# A314-600_v1_0.net
KiCad netlist of a schematic drawn in EAGLE
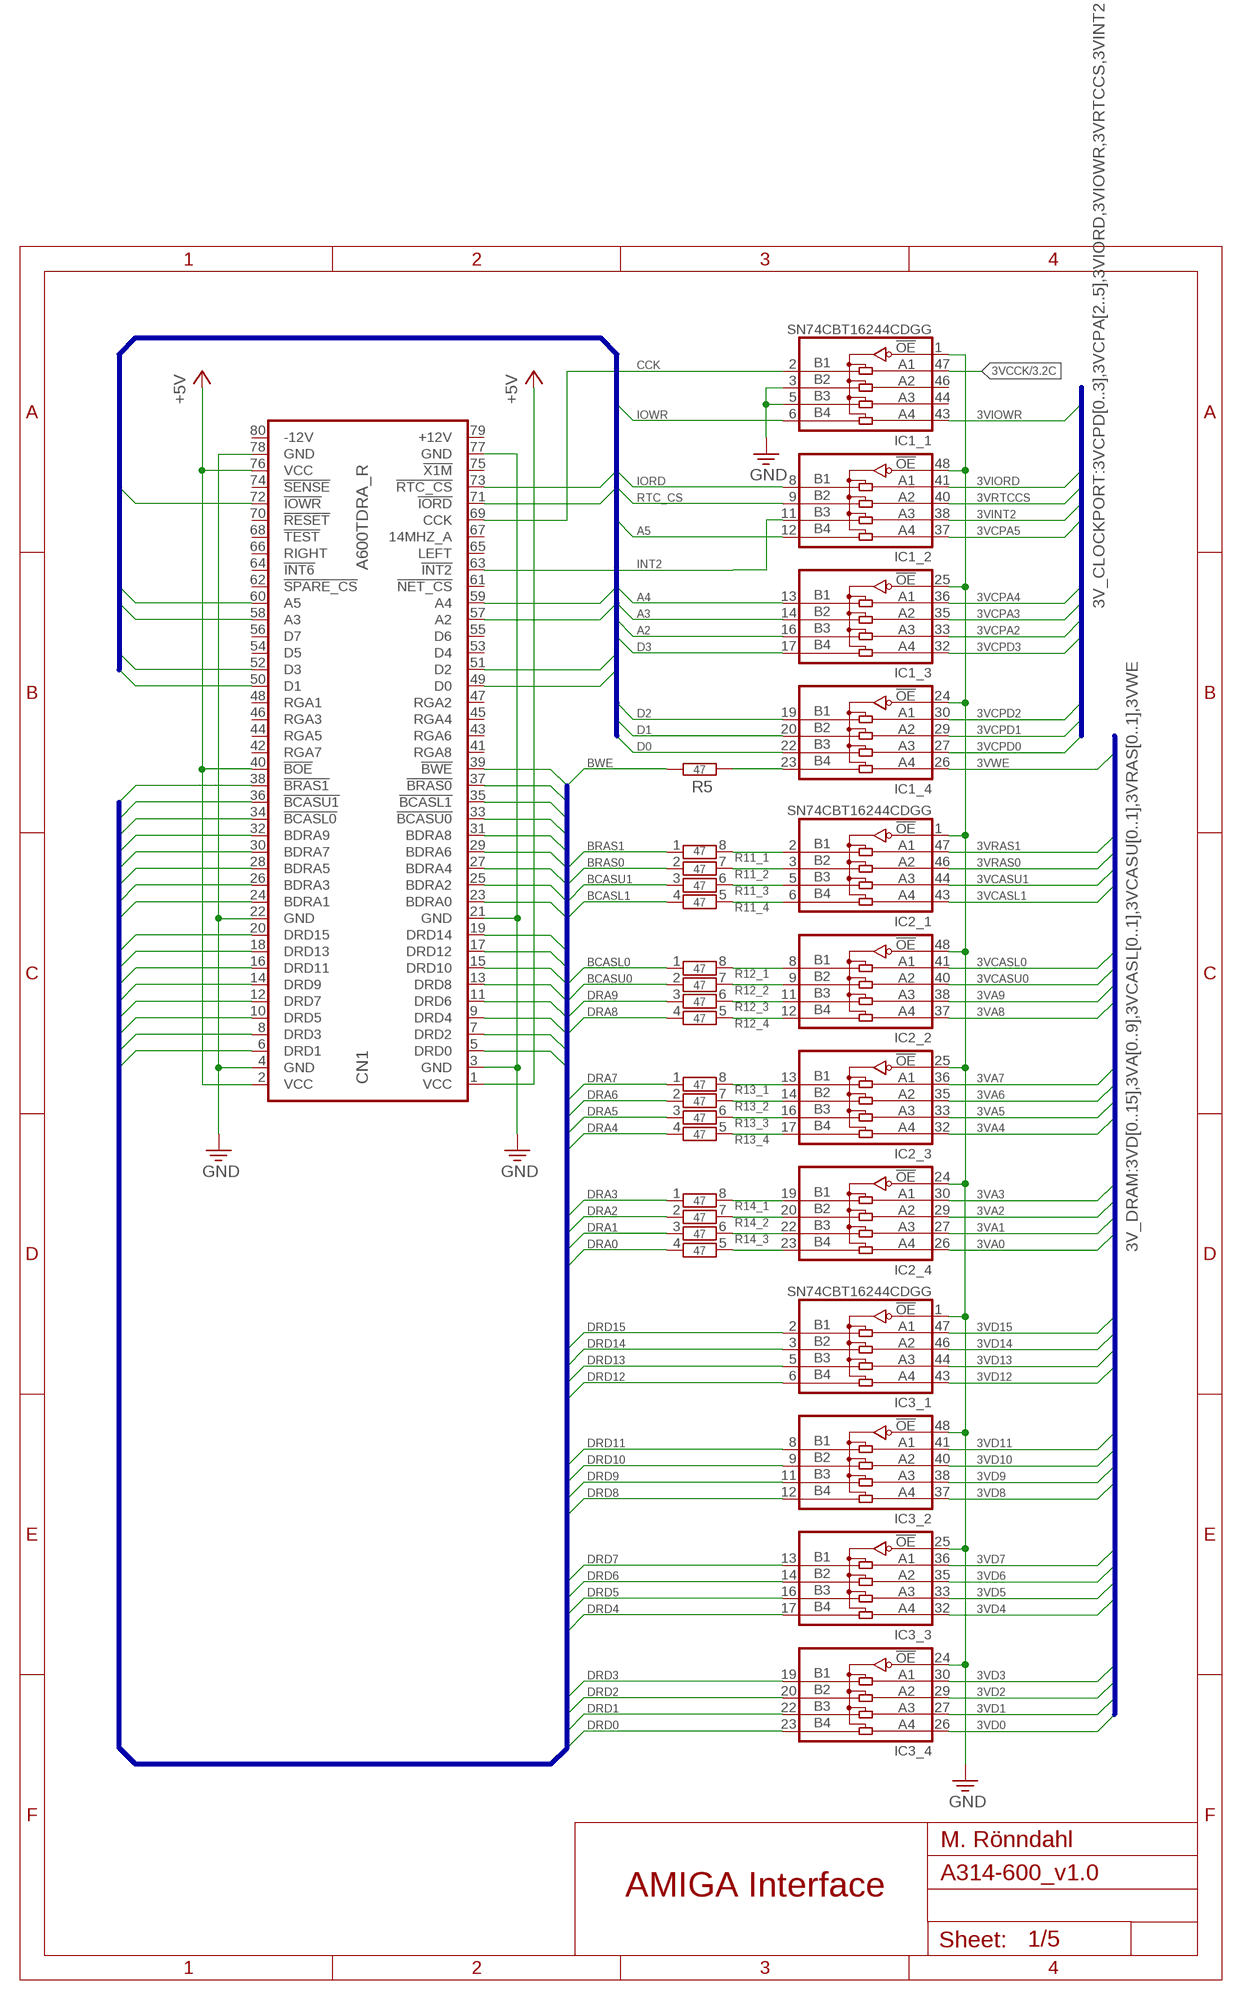
[diagram p0: schematic, sheet 1]
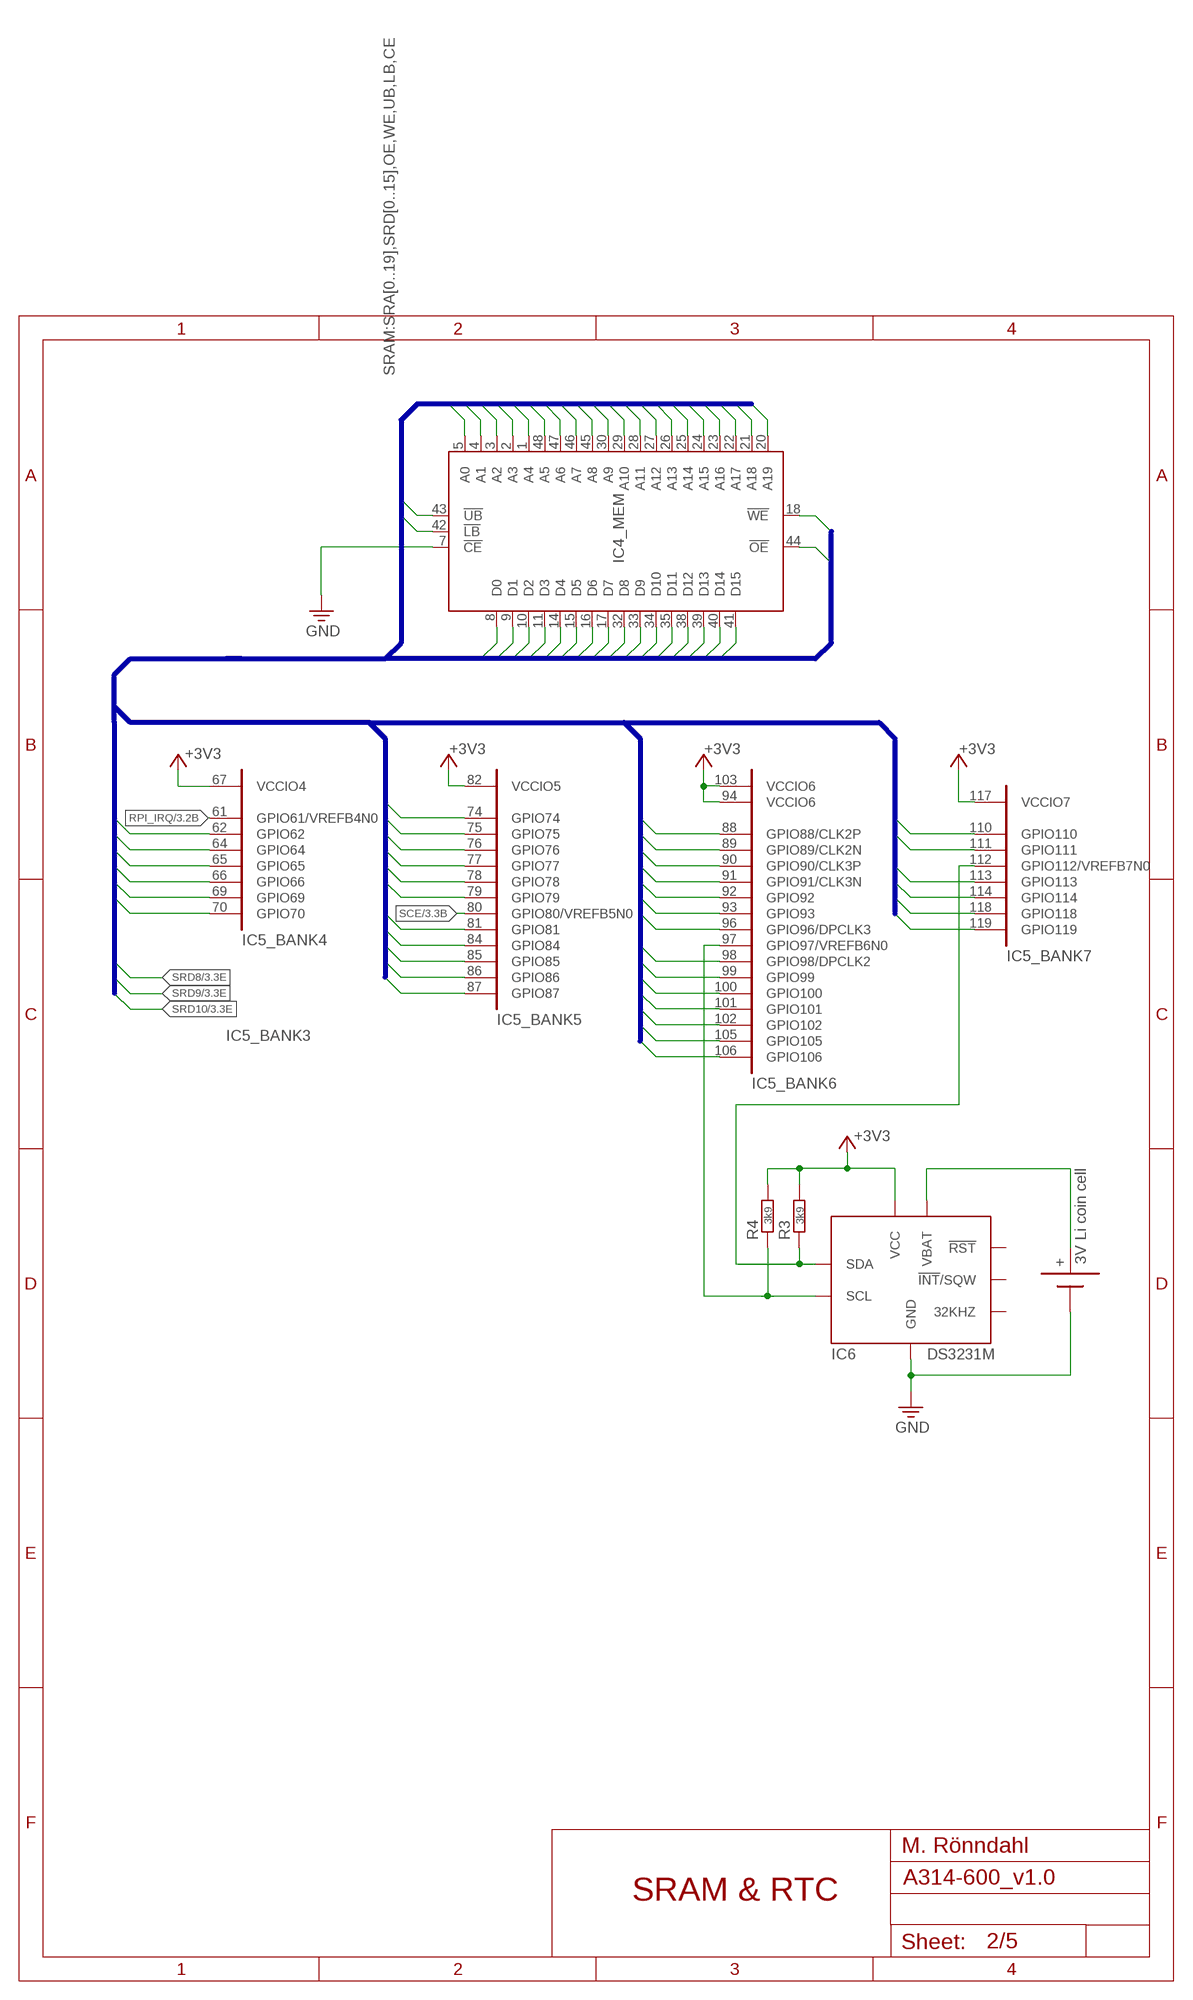
[diagram p1: schematic, sheet 2]
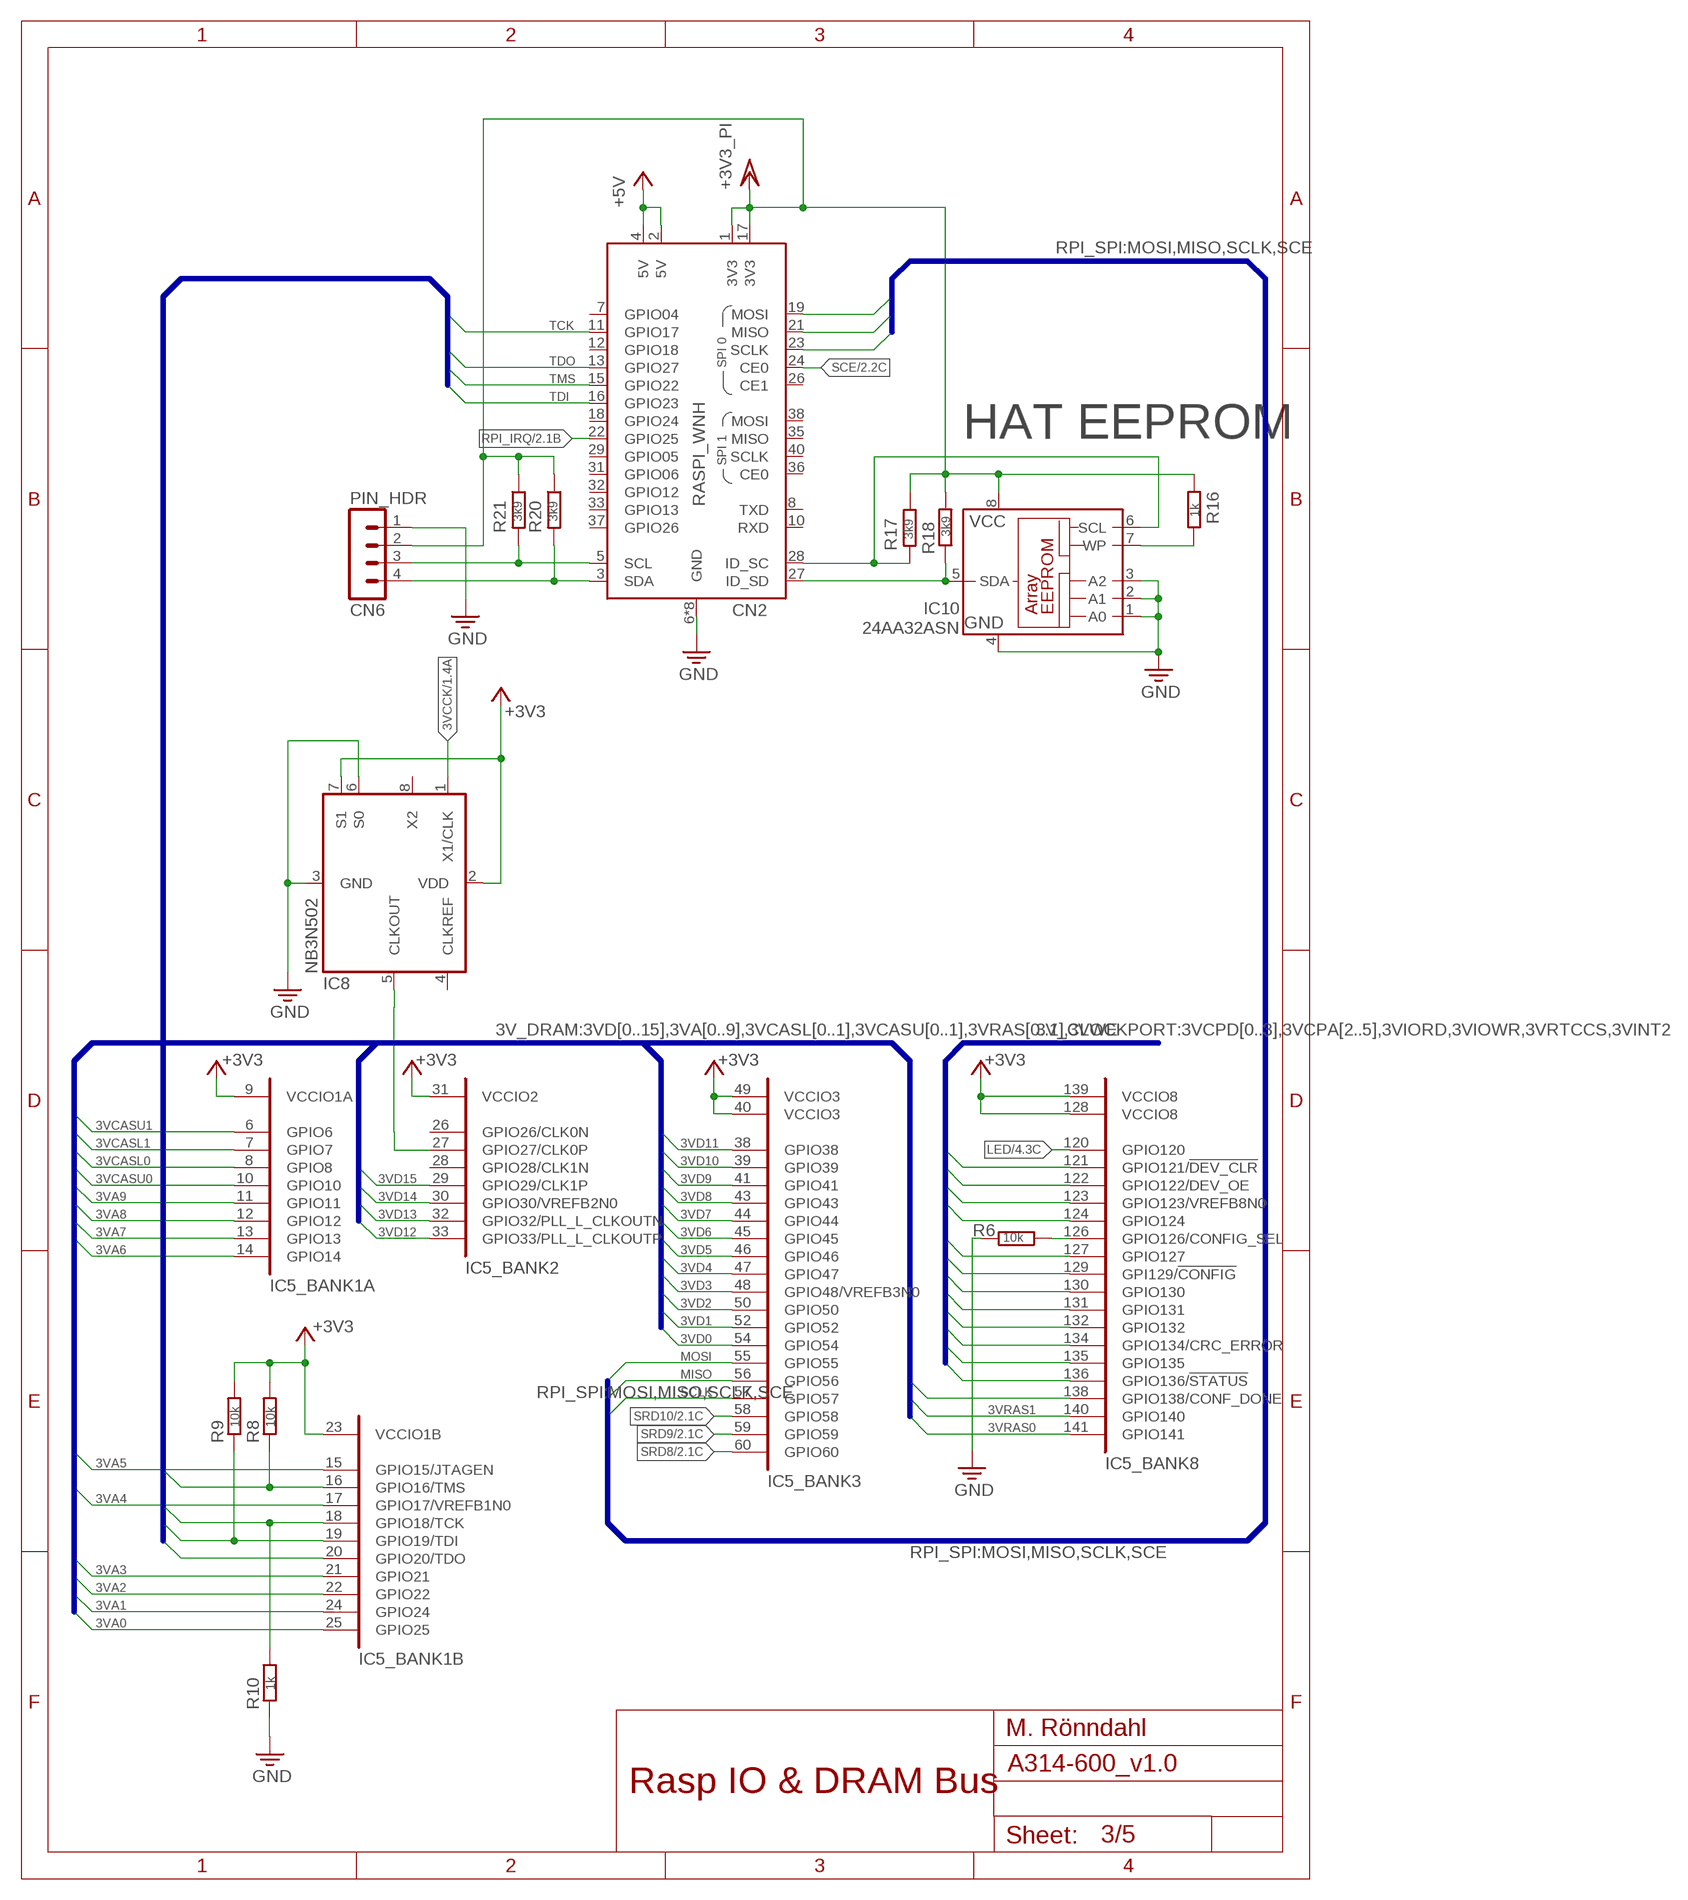
[diagram p2: schematic, sheet 3]
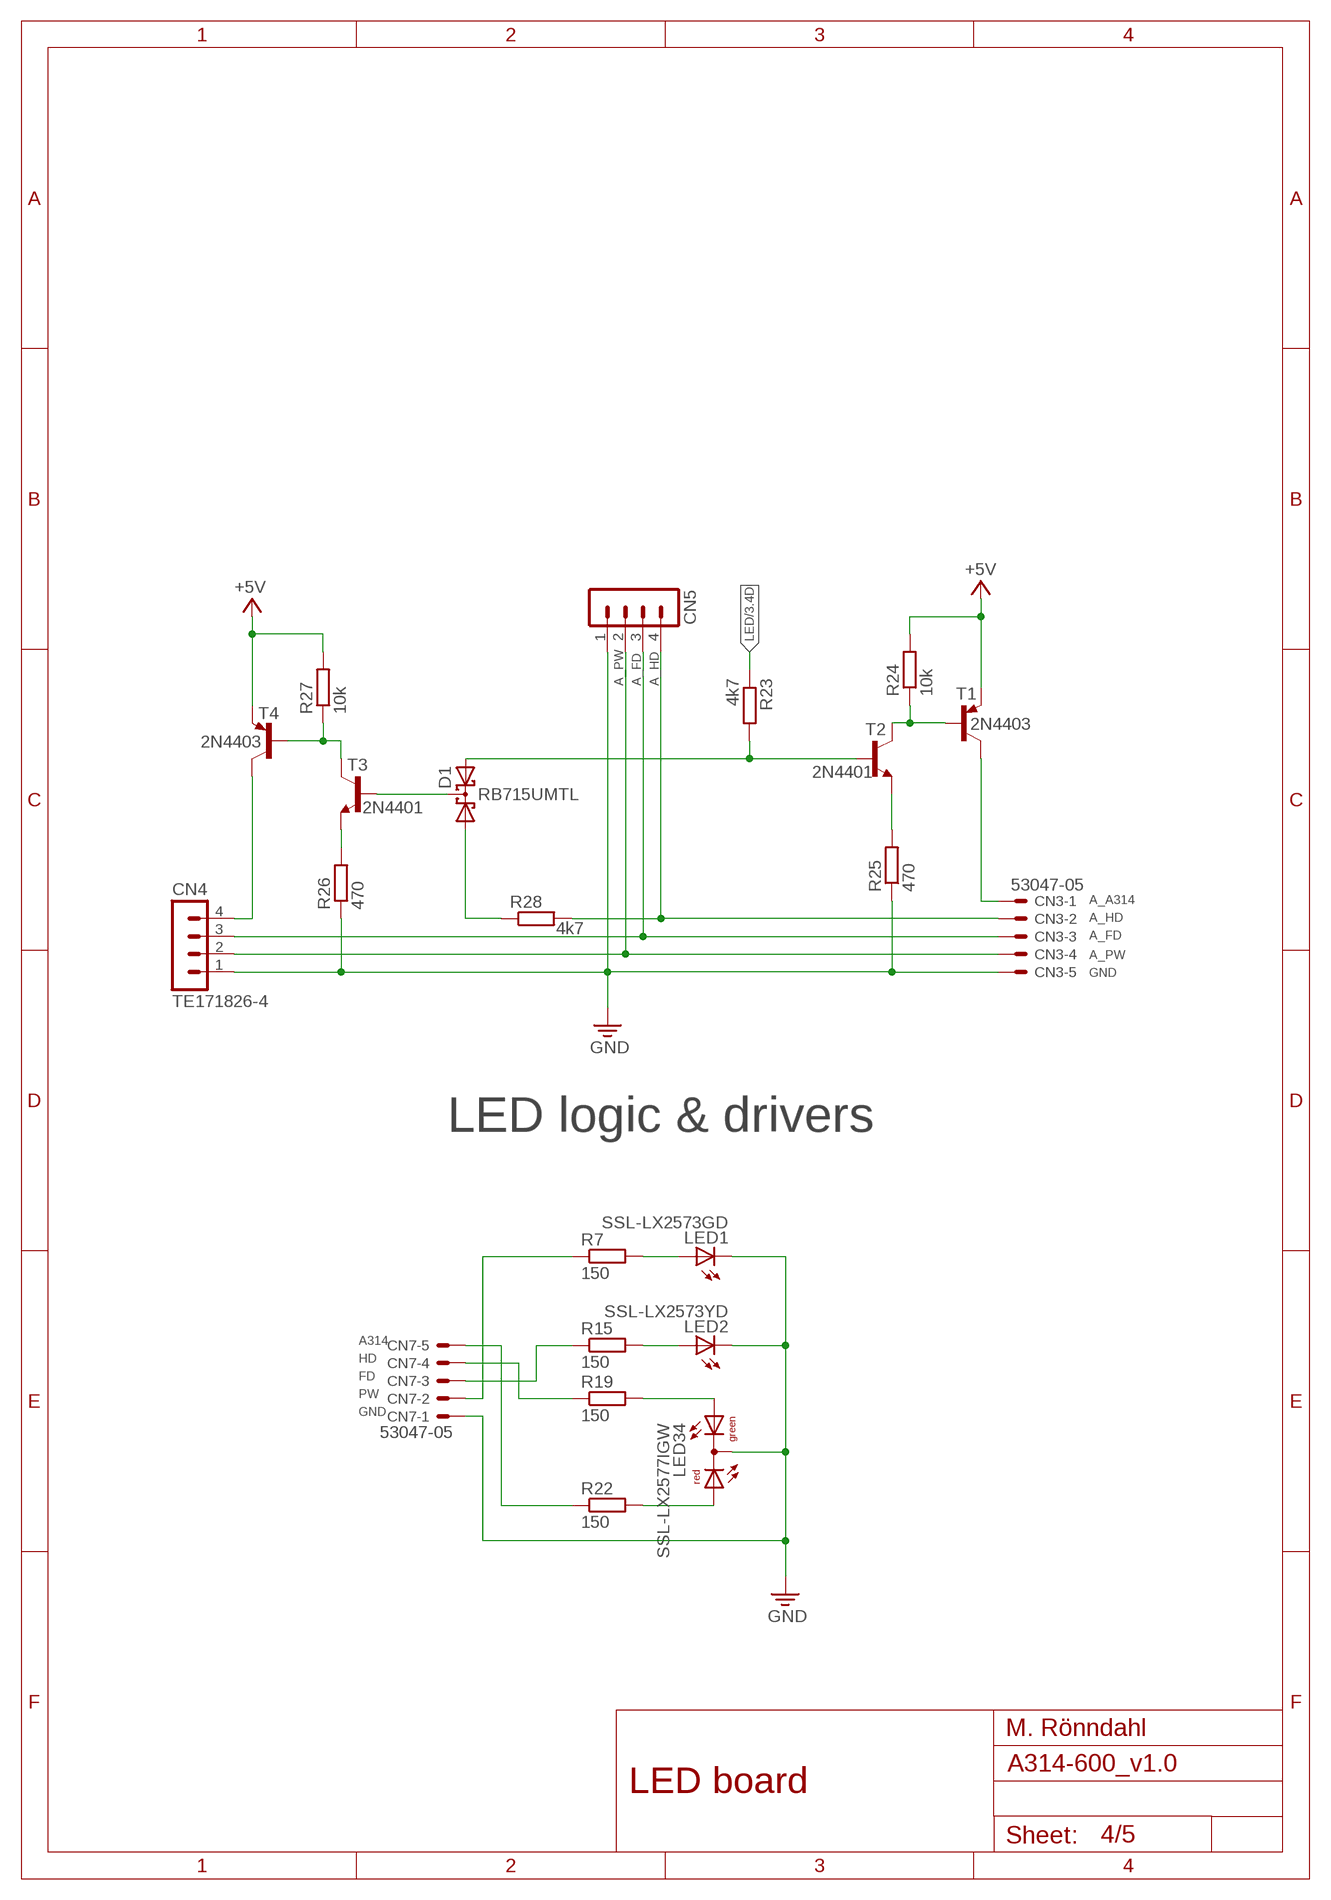
[diagram p3: schematic, sheet 4]
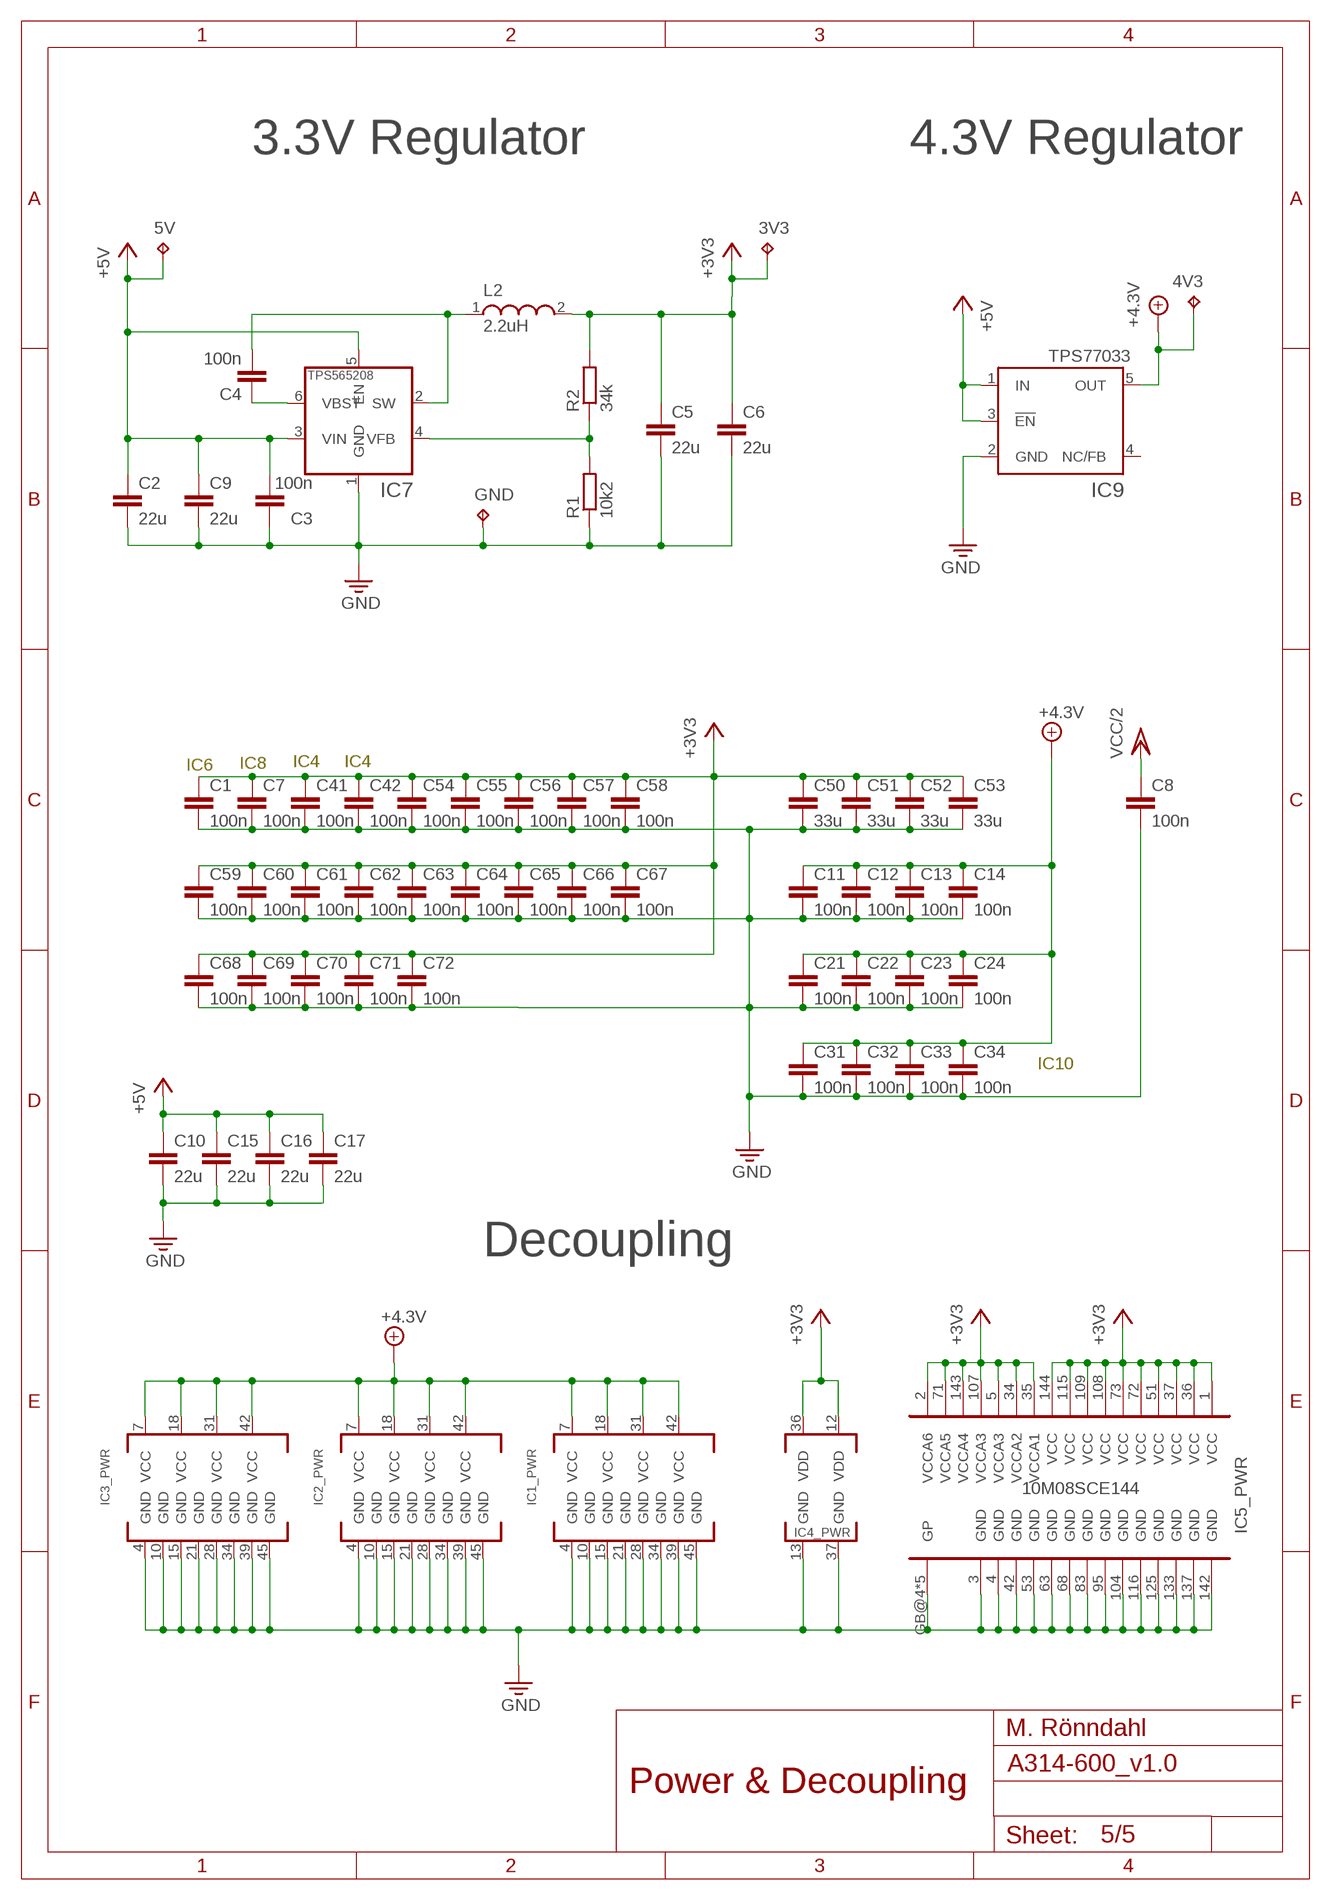
[diagram p4: schematic, sheet 5]

(export (version "E")
  (design (tool "Eeschema 10.0.6"))
  (components
    (comp (ref "CN2")
      (value "RASPI_WNH")
      (footprint "eagle-import:RASPBERRYPIZEROW_NO_HOLES")
      (libsource (lib "eagle-import") (part "RASPI_WNH"))
    )
    (comp (ref "CN6")
      (value "PIN_HDR")
      (footprint "eagle-import:MA04-1")
      (libsource (lib "eagle-import") (part "MA04-1"))
    )
    (comp (ref "IC5")
      (value "10M08SCE144")
      (footprint "eagle-import:SQFP-S-20X20-144")
      (libsource (lib "eagle-import") (part "10M08SCE144"))
    )
    (comp (ref "IC8")
      (value "NB3N502")
      (footprint "eagle-import:SO08")
      (libsource (lib "eagle-import") (part "NB3N502"))
    )
    (comp (ref "IC10")
      (value "24AA32ASN")
      (footprint "eagle-import:SO-08")
      (fields (field (name "MF") "MICROCHIP") (field (name "MPN") "24AA32A-I/SN"))
      (libsource (lib "eagle-import") (part "24SNAA32A"))
    )
    (comp (ref "R6")
      (value "10k")
      (footprint "eagle-import:R0603")
      (libsource (lib "eagle-import") (part "R-EU_R0603"))
    )
    (comp (ref "R8")
      (value "10k")
      (footprint "eagle-import:R0603")
      (libsource (lib "eagle-import") (part "R-EU_R0603"))
    )
    (comp (ref "R9")
      (value "10k")
      (footprint "eagle-import:R0603")
      (libsource (lib "eagle-import") (part "R-EU_R0603"))
    )
    (comp (ref "R10")
      (value "1k")
      (footprint "eagle-import:R0603")
      (libsource (lib "eagle-import") (part "R-EU_R0603"))
    )
    (comp (ref "R16")
      (value "1k")
      (footprint "eagle-import:R0603")
      (libsource (lib "eagle-import") (part "R-EU_R0603"))
    )
    (comp (ref "R17")
      (value "3k9")
      (footprint "eagle-import:R0603")
      (libsource (lib "eagle-import") (part "R-EU_R0603"))
    )
    (comp (ref "R18")
      (value "3k9")
      (footprint "eagle-import:R0603")
      (libsource (lib "eagle-import") (part "R-EU_R0603"))
    )
    (comp (ref "R20")
      (value "3k9")
      (footprint "eagle-import:R0603")
      (libsource (lib "eagle-import") (part "R-EU_R0603"))
    )
    (comp (ref "R21")
      (value "3k9")
      (footprint "eagle-import:R0603")
      (libsource (lib "eagle-import") (part "R-EU_R0603"))
    )
    (comp (ref "CN1")
      (value "A600TDRA_R")
      (footprint "eagle-import:CE-2X40_1.27_R")
      (libsource (lib "eagle-import") (part "A600TDRA_R"))
    )
    (comp (ref "IC1")
      (value "SN74CBT16244CDGG")
      (footprint "eagle-import:PSOP-DGG48")
      (libsource (lib "eagle-import") (part "SN74CBT16244CDGG"))
    )
    (comp (ref "IC2")
      (value "SN74CBT16244CDGG")
      (footprint "eagle-import:PSOP-DGG48")
      (libsource (lib "eagle-import") (part "SN74CBT16244CDGG"))
    )
    (comp (ref "IC3")
      (value "SN74CBT16244CDGG")
      (footprint "eagle-import:PSOP-DGG48")
      (libsource (lib "eagle-import") (part "SN74CBT16244CDGG"))
    )
    (comp (ref "R5")
      (value "47")
      (footprint "eagle-import:R0603")
      (libsource (lib "eagle-import") (part "R-EU_R0603"))
    )
    (comp (ref "R11")
      (value "47")
      (footprint "eagle-import:CTS742C083")
      (libsource (lib "eagle-import") (part "CTS742C083_S"))
    )
    (comp (ref "R12")
      (value "47")
      (footprint "eagle-import:CTS742C083")
      (libsource (lib "eagle-import") (part "CTS742C083_S"))
    )
    (comp (ref "R13")
      (value "47")
      (footprint "eagle-import:CTS742C083")
      (libsource (lib "eagle-import") (part "CTS742C083_S"))
    )
    (comp (ref "R14")
      (value "47")
      (footprint "eagle-import:CTS742C083")
      (libsource (lib "eagle-import") (part "CTS742C083_S"))
    )
    (comp (ref "BAT1")
      (value "CR2025/CR2032TH")
      (footprint "eagle-import:LINX20XX-THM")
      (libsource (lib "eagle-import") (part "CR2025/CR2032TH"))
    )
    (comp (ref "IC4")
      (value "IS61WV102416FBLL-TLI")
      (footprint "eagle-import:TSOP-1_48L_12X20")
      (libsource (lib "eagle-import") (part "IS61WV102416FBLL-TLI"))
    )
    (comp (ref "IC6")
      (value "DS3231M")
      (footprint "eagle-import:SOIC8")
      (libsource (lib "eagle-import") (part "DS3231M"))
    )
    (comp (ref "R3")
      (value "3k9")
      (footprint "eagle-import:R0603")
      (libsource (lib "eagle-import") (part "R-EU_R0603"))
    )
    (comp (ref "R4")
      (value "3k9")
      (footprint "eagle-import:R0603")
      (libsource (lib "eagle-import") (part "R-EU_R0603"))
    )
    (comp (ref "CN3")
      (value "53047-05")
      (footprint "eagle-import:53047-05")
      (fields (field (name "MF") "MOLEX") (field (name "MPN") "53047-0510"))
      (libsource (lib "eagle-import") (part "53?-05047"))
    )
    (comp (ref "CN4")
      (value "TE171826-4")
      (footprint "eagle-import:FLOPPY_PWR")
      (libsource (lib "eagle-import") (part "TE171826-4"))
    )
    (comp (ref "CN5")
      (value "MA04-1")
      (footprint "eagle-import:MA04-1")
      (libsource (lib "eagle-import") (part "con-various_MA04-1"))
    )
    (comp (ref "CN7")
      (value "53047-05")
      (footprint "eagle-import:53047-05")
      (fields (field (name "MF") "MOLEX") (field (name "MPN") "53047-0510"))
      (libsource (lib "eagle-import") (part "53?-05047"))
    )
    (comp (ref "D1")
      (value "RB715UMTL")
      (footprint "eagle-import:SOT23")
      (libsource (lib "eagle-import") (part "BAS40-05"))
    )
    (comp (ref "LED1")
      (value "SSL-LX2573GD")
      (footprint "eagle-import:LED2X5")
      (libsource (lib "eagle-import") (part "LEDSQR2X5"))
    )
    (comp (ref "LED2")
      (value "SSL-LX2573YD")
      (footprint "eagle-import:LED2X5")
      (libsource (lib "eagle-import") (part "LEDSQR2X5"))
    )
    (comp (ref "LED34")
      (value "SSL-LX2577IGW")
      (footprint "eagle-import:DUOLED2X5")
      (libsource (lib "eagle-import") (part "DUOLED2X5"))
    )
    (comp (ref "R7")
      (value "150")
      (footprint "eagle-import:R0603")
      (libsource (lib "eagle-import") (part "R-EU_R0603"))
    )
    (comp (ref "R15")
      (value "150")
      (footprint "eagle-import:R0603")
      (libsource (lib "eagle-import") (part "R-EU_R0603"))
    )
    (comp (ref "R19")
      (value "150")
      (footprint "eagle-import:R0603")
      (libsource (lib "eagle-import") (part "R-EU_R0603"))
    )
    (comp (ref "R22")
      (value "150")
      (footprint "eagle-import:R0603")
      (libsource (lib "eagle-import") (part "R-EU_R0603"))
    )
    (comp (ref "R23")
      (value "4k7")
      (footprint "eagle-import:R0603")
      (libsource (lib "eagle-import") (part "R-EU_R0603"))
    )
    (comp (ref "R24")
      (value "10k")
      (footprint "eagle-import:R0603")
      (libsource (lib "eagle-import") (part "R-EU_R0603"))
    )
    (comp (ref "R25")
      (value "470")
      (footprint "eagle-import:R0603")
      (libsource (lib "eagle-import") (part "R-EU_R0603"))
    )
    (comp (ref "R26")
      (value "470")
      (footprint "eagle-import:R0603")
      (libsource (lib "eagle-import") (part "R-EU_R0603"))
    )
    (comp (ref "R27")
      (value "10k")
      (footprint "eagle-import:R0603")
      (libsource (lib "eagle-import") (part "R-EU_R0603"))
    )
    (comp (ref "R28")
      (value "4k7")
      (footprint "eagle-import:R0603")
      (libsource (lib "eagle-import") (part "R-EU_R0603"))
    )
    (comp (ref "T1")
      (value "2N4403")
      (footprint "eagle-import:SOT23-BEC")
      (libsource (lib "eagle-import") (part "-PNP-SOT23-BECMMBT4403LT1"))
    )
    (comp (ref "T2")
      (value "2N4401")
      (footprint "eagle-import:SOT23-BEC")
      (libsource (lib "eagle-import") (part "-NPN-SOT23-BECMMBT4401LT1"))
    )
    (comp (ref "T3")
      (value "2N4401")
      (footprint "eagle-import:SOT23-BEC")
      (libsource (lib "eagle-import") (part "-NPN-SOT23-BECMMBT4401LT1"))
    )
    (comp (ref "T4")
      (value "2N4403")
      (footprint "eagle-import:SOT23-BEC")
      (libsource (lib "eagle-import") (part "-PNP-SOT23-BECMMBT4403LT1"))
    )
    (comp (ref "3V3")
      (value "TPPAD1-13")
      (footprint "eagle-import:P1-13")
      (libsource (lib "eagle-import") (part "TPPAD1-13"))
    )
    (comp (ref "4V3")
      (value "TPPAD1-13")
      (footprint "eagle-import:P1-13")
      (libsource (lib "eagle-import") (part "TPPAD1-13"))
    )
    (comp (ref "5V")
      (value "TPPAD1-13")
      (footprint "eagle-import:P1-13")
      (libsource (lib "eagle-import") (part "TPPAD1-13"))
    )
    (comp (ref "C1")
      (value "100n")
      (footprint "eagle-import:C0603")
      (libsource (lib "eagle-import") (part "C-EUC0603"))
    )
    (comp (ref "C2")
      (value "22u")
      (footprint "eagle-import:C0805")
      (libsource (lib "eagle-import") (part "C-EUC0805"))
    )
    (comp (ref "C3")
      (value "100n")
      (footprint "eagle-import:C0603")
      (libsource (lib "eagle-import") (part "C-EUC0603"))
    )
    (comp (ref "C4")
      (value "100n")
      (footprint "eagle-import:C0603")
      (libsource (lib "eagle-import") (part "C-EUC0603"))
    )
    (comp (ref "C5")
      (value "22u")
      (footprint "eagle-import:C0805")
      (libsource (lib "eagle-import") (part "C-EUC0805"))
    )
    (comp (ref "C6")
      (value "22u")
      (footprint "eagle-import:C0805")
      (libsource (lib "eagle-import") (part "C-EUC0805"))
    )
    (comp (ref "C7")
      (value "100n")
      (footprint "eagle-import:C0603")
      (libsource (lib "eagle-import") (part "C-EUC0603"))
    )
    (comp (ref "C8")
      (value "100n")
      (footprint "eagle-import:C0603")
      (libsource (lib "eagle-import") (part "C-EUC0603"))
    )
    (comp (ref "C9")
      (value "22u")
      (footprint "eagle-import:C0805")
      (libsource (lib "eagle-import") (part "C-EUC0805"))
    )
    (comp (ref "C10")
      (value "22u")
      (footprint "eagle-import:C0805")
      (libsource (lib "eagle-import") (part "C-EUC0805"))
    )
    (comp (ref "C11")
      (value "100n")
      (footprint "eagle-import:C0603")
      (libsource (lib "eagle-import") (part "C-EUC0603"))
    )
    (comp (ref "C12")
      (value "100n")
      (footprint "eagle-import:C0603")
      (libsource (lib "eagle-import") (part "C-EUC0603"))
    )
    (comp (ref "C13")
      (value "100n")
      (footprint "eagle-import:C0603")
      (libsource (lib "eagle-import") (part "C-EUC0603"))
    )
    (comp (ref "C14")
      (value "100n")
      (footprint "eagle-import:C0603")
      (libsource (lib "eagle-import") (part "C-EUC0603"))
    )
    (comp (ref "C15")
      (value "22u")
      (footprint "eagle-import:C0805")
      (libsource (lib "eagle-import") (part "C-EUC0805"))
    )
    (comp (ref "C16")
      (value "22u")
      (footprint "eagle-import:C0805")
      (libsource (lib "eagle-import") (part "C-EUC0805"))
    )
    (comp (ref "C17")
      (value "22u")
      (footprint "eagle-import:C0805")
      (libsource (lib "eagle-import") (part "C-EUC0805"))
    )
    (comp (ref "C21")
      (value "100n")
      (footprint "eagle-import:C0603")
      (libsource (lib "eagle-import") (part "C-EUC0603"))
    )
    (comp (ref "C22")
      (value "100n")
      (footprint "eagle-import:C0603")
      (libsource (lib "eagle-import") (part "C-EUC0603"))
    )
    (comp (ref "C23")
      (value "100n")
      (footprint "eagle-import:C0603")
      (libsource (lib "eagle-import") (part "C-EUC0603"))
    )
    (comp (ref "C24")
      (value "100n")
      (footprint "eagle-import:C0603")
      (libsource (lib "eagle-import") (part "C-EUC0603"))
    )
    (comp (ref "C31")
      (value "100n")
      (footprint "eagle-import:C0603")
      (libsource (lib "eagle-import") (part "C-EUC0603"))
    )
    (comp (ref "C32")
      (value "100n")
      (footprint "eagle-import:C0603")
      (libsource (lib "eagle-import") (part "C-EUC0603"))
    )
    (comp (ref "C33")
      (value "100n")
      (footprint "eagle-import:C0603")
      (libsource (lib "eagle-import") (part "C-EUC0603"))
    )
    (comp (ref "C34")
      (value "100n")
      (footprint "eagle-import:C0603")
      (libsource (lib "eagle-import") (part "C-EUC0603"))
    )
    (comp (ref "C41")
      (value "100n")
      (footprint "eagle-import:C0603")
      (libsource (lib "eagle-import") (part "C-EUC0603"))
    )
    (comp (ref "C42")
      (value "100n")
      (footprint "eagle-import:C0603")
      (libsource (lib "eagle-import") (part "C-EUC0603"))
    )
    (comp (ref "C50")
      (value "33u")
      (footprint "eagle-import:C0805")
      (libsource (lib "eagle-import") (part "C-EUC0805"))
    )
    (comp (ref "C51")
      (value "33u")
      (footprint "eagle-import:C0805")
      (libsource (lib "eagle-import") (part "C-EUC0805"))
    )
    (comp (ref "C52")
      (value "33u")
      (footprint "eagle-import:C0805")
      (libsource (lib "eagle-import") (part "C-EUC0805"))
    )
    (comp (ref "C53")
      (value "33u")
      (footprint "eagle-import:C0805")
      (libsource (lib "eagle-import") (part "C-EUC0805"))
    )
    (comp (ref "C54")
      (value "100n")
      (footprint "eagle-import:C0603")
      (libsource (lib "eagle-import") (part "C-EUC0603"))
    )
    (comp (ref "C55")
      (value "100n")
      (footprint "eagle-import:C0603")
      (libsource (lib "eagle-import") (part "C-EUC0603"))
    )
    (comp (ref "C56")
      (value "100n")
      (footprint "eagle-import:C0603")
      (libsource (lib "eagle-import") (part "C-EUC0603"))
    )
    (comp (ref "C57")
      (value "100n")
      (footprint "eagle-import:C0603")
      (libsource (lib "eagle-import") (part "C-EUC0603"))
    )
    (comp (ref "C58")
      (value "100n")
      (footprint "eagle-import:C0603")
      (libsource (lib "eagle-import") (part "C-EUC0603"))
    )
    (comp (ref "C59")
      (value "100n")
      (footprint "eagle-import:C0603")
      (libsource (lib "eagle-import") (part "C-EUC0603"))
    )
    (comp (ref "C60")
      (value "100n")
      (footprint "eagle-import:C0603")
      (libsource (lib "eagle-import") (part "C-EUC0603"))
    )
    (comp (ref "C61")
      (value "100n")
      (footprint "eagle-import:C0603")
      (libsource (lib "eagle-import") (part "C-EUC0603"))
    )
    (comp (ref "C62")
      (value "100n")
      (footprint "eagle-import:C0603")
      (libsource (lib "eagle-import") (part "C-EUC0603"))
    )
    (comp (ref "C63")
      (value "100n")
      (footprint "eagle-import:C0603")
      (libsource (lib "eagle-import") (part "C-EUC0603"))
    )
    (comp (ref "C64")
      (value "100n")
      (footprint "eagle-import:C0603")
      (libsource (lib "eagle-import") (part "C-EUC0603"))
    )
    (comp (ref "C65")
      (value "100n")
      (footprint "eagle-import:C0603")
      (libsource (lib "eagle-import") (part "C-EUC0603"))
    )
    (comp (ref "C66")
      (value "100n")
      (footprint "eagle-import:C0603")
      (libsource (lib "eagle-import") (part "C-EUC0603"))
    )
    (comp (ref "C67")
      (value "100n")
      (footprint "eagle-import:C0603")
      (libsource (lib "eagle-import") (part "C-EUC0603"))
    )
    (comp (ref "C68")
      (value "100n")
      (footprint "eagle-import:C0603")
      (libsource (lib "eagle-import") (part "C-EUC0603"))
    )
    (comp (ref "C69")
      (value "100n")
      (footprint "eagle-import:C0603")
      (libsource (lib "eagle-import") (part "C-EUC0603"))
    )
    (comp (ref "C70")
      (value "100n")
      (footprint "eagle-import:C0603")
      (libsource (lib "eagle-import") (part "C-EUC0603"))
    )
    (comp (ref "C71")
      (value "100n")
      (footprint "eagle-import:C0603")
      (libsource (lib "eagle-import") (part "C-EUC0603"))
    )
    (comp (ref "C72")
      (value "100n")
      (footprint "eagle-import:C0603")
      (libsource (lib "eagle-import") (part "C-EUC0603"))
    )
    (comp (ref "GND")
      (value "TPPAD1-13")
      (footprint "eagle-import:P1-13")
      (libsource (lib "eagle-import") (part "TPPAD1-13"))
    )
    (comp (ref "IC7")
      (value "TPS565208")
      (footprint "eagle-import:THIN_SO23")
      (libsource (lib "eagle-import") (part "TPS565208DDC"))
    )
    (comp (ref "IC9")
      (value "TPS77033")
      (footprint "eagle-import:SOT23-DBV")
      (fields (field (name "MF") "TEXAS INSTRUMENTS") (field (name "MPN") "TPS77033DBVT"))
      (libsource (lib "eagle-import") (part "TPS77033"))
    )
    (comp (ref "L2")
      (value "2.2uH")
      (footprint "eagle-import:WE-TPC_1028_1038")
      (libsource (lib "eagle-import") (part "WE-TPC_1028/1038"))
    )
    (comp (ref "R1")
      (value "10k2")
      (footprint "eagle-import:R0603")
      (libsource (lib "eagle-import") (part "R-EU_R0603"))
    )
    (comp (ref "R2")
      (value "34k")
      (footprint "eagle-import:R0603")
      (libsource (lib "eagle-import") (part "R-EU_R0603"))
    )
  )
  (nets
    (net (code "3") (name "+3V3") (class "Default")
      (node (ref "3V3") (pin "TP") (pinfunction "TP_TP") (pintype "input"))
      (node (ref "C1") (pin "1") (pinfunction "1_1") (pintype "passive"))
      (node (ref "C41") (pin "1") (pinfunction "1_1") (pintype "passive"))
      (node (ref "C42") (pin "1") (pinfunction "1_1") (pintype "passive"))
      (node (ref "C5") (pin "1") (pinfunction "1_1") (pintype "passive"))
      (node (ref "C50") (pin "1") (pinfunction "1_1") (pintype "passive"))
      (node (ref "C51") (pin "1") (pinfunction "1_1") (pintype "passive"))
      (node (ref "C52") (pin "1") (pinfunction "1_1") (pintype "passive"))
      (node (ref "C53") (pin "1") (pinfunction "1_1") (pintype "passive"))
      (node (ref "C54") (pin "1") (pinfunction "1_1") (pintype "passive"))
      (node (ref "C55") (pin "1") (pinfunction "1_1") (pintype "passive"))
      (node (ref "C56") (pin "1") (pinfunction "1_1") (pintype "passive"))
      (node (ref "C57") (pin "1") (pinfunction "1_1") (pintype "passive"))
      (node (ref "C58") (pin "1") (pinfunction "1_1") (pintype "passive"))
      (node (ref "C59") (pin "1") (pinfunction "1_1") (pintype "passive"))
      (node (ref "C6") (pin "1") (pinfunction "1_1") (pintype "passive"))
      (node (ref "C60") (pin "1") (pinfunction "1_1") (pintype "passive"))
      (node (ref "C61") (pin "1") (pinfunction "1_1") (pintype "passive"))
      (node (ref "C62") (pin "1") (pinfunction "1_1") (pintype "passive"))
      (node (ref "C63") (pin "1") (pinfunction "1_1") (pintype "passive"))
      (node (ref "C64") (pin "1") (pinfunction "1_1") (pintype "passive"))
      (node (ref "C65") (pin "1") (pinfunction "1_1") (pintype "passive"))
      (node (ref "C66") (pin "1") (pinfunction "1_1") (pintype "passive"))
      (node (ref "C67") (pin "1") (pinfunction "1_1") (pintype "passive"))
      (node (ref "C68") (pin "1") (pinfunction "1_1") (pintype "passive"))
      (node (ref "C69") (pin "1") (pinfunction "1_1") (pintype "passive"))
      (node (ref "C7") (pin "1") (pinfunction "1_1") (pintype "passive"))
      (node (ref "C70") (pin "1") (pinfunction "1_1") (pintype "passive"))
      (node (ref "C71") (pin "1") (pinfunction "1_1") (pintype "passive"))
      (node (ref "C72") (pin "1") (pinfunction "1_1") (pintype "passive"))
      (node (ref "IC4") (pin "12") (pinfunction "VDD_12") (pintype "bidirectional"))
      (node (ref "IC4") (pin "36") (pinfunction "VDD_36") (pintype "bidirectional"))
      (node (ref "IC5") (pin "1") (pinfunction "VCC_1") (pintype "power_in"))
      (node (ref "IC5") (pin "103") (pinfunction "VCCIO6_103") (pintype "power_in"))
      (node (ref "IC5") (pin "107") (pinfunction "VCCA3_107") (pintype "power_in"))
      (node (ref "IC5") (pin "108") (pinfunction "VCC_108") (pintype "power_in"))
      (node (ref "IC5") (pin "109") (pinfunction "VCC_109") (pintype "power_in"))
      (node (ref "IC5") (pin "115") (pinfunction "VCC_115") (pintype "power_in"))
      (node (ref "IC5") (pin "117") (pinfunction "VCCIO7_117") (pintype "power_in"))
      (node (ref "IC5") (pin "128") (pinfunction "VCCIO8_128") (pintype "power_in"))
      (node (ref "IC5") (pin "139") (pinfunction "VCCIO8_139") (pintype "power_in"))
      (node (ref "IC5") (pin "143") (pinfunction "VCCA4_143") (pintype "power_in"))
      (node (ref "IC5") (pin "144") (pinfunction "VCC_144") (pintype "power_in"))
      (node (ref "IC5") (pin "2") (pinfunction "VCCA6_2") (pintype "power_in"))
      (node (ref "IC5") (pin "23") (pinfunction "VCCIO1B_23") (pintype "power_in"))
      (node (ref "IC5") (pin "31") (pinfunction "VCCIO2_31") (pintype "power_in"))
      (node (ref "IC5") (pin "34") (pinfunction "VCCA2_34") (pintype "power_in"))
      (node (ref "IC5") (pin "35") (pinfunction "VCCA1_35") (pintype "power_in"))
      (node (ref "IC5") (pin "36") (pinfunction "VCC_36") (pintype "power_in"))
      (node (ref "IC5") (pin "37") (pinfunction "VCC_37") (pintype "power_in"))
      (node (ref "IC5") (pin "40") (pinfunction "VCCIO3_40") (pintype "power_in"))
      (node (ref "IC5") (pin "49") (pinfunction "VCCIO3_49") (pintype "power_in"))
      (node (ref "IC5") (pin "5") (pinfunction "VCCA3_5") (pintype "power_in"))
      (node (ref "IC5") (pin "51") (pinfunction "VCC_51") (pintype "power_in"))
      (node (ref "IC5") (pin "67") (pinfunction "VCCIO4_67") (pintype "power_in"))
      (node (ref "IC5") (pin "71") (pinfunction "VCCA5_71") (pintype "power_in"))
      (node (ref "IC5") (pin "72") (pinfunction "VCC_72") (pintype "power_in"))
      (node (ref "IC5") (pin "73") (pinfunction "VCC_73") (pintype "power_in"))
      (node (ref "IC5") (pin "82") (pinfunction "VCCIO5_82") (pintype "power_in"))
      (node (ref "IC5") (pin "9") (pinfunction "VCCIO1A_9") (pintype "power_in"))
      (node (ref "IC5") (pin "94") (pinfunction "VCCIO6_94") (pintype "power_in"))
      (node (ref "IC6") (pin "2") (pinfunction "VCC_2") (pintype "power_in"))
      (node (ref "IC8") (pin "2") (pinfunction "VDD_2") (pintype "power_in"))
      (node (ref "IC8") (pin "7") (pinfunction "S1_7") (pintype "input"))
      (node (ref "L2") (pin "2") (pinfunction "2_2") (pintype "passive"))
      (node (ref "R2") (pin "2") (pinfunction "2_2") (pintype "passive"))
      (node (ref "R3") (pin "2") (pinfunction "2_2") (pintype "passive"))
      (node (ref "R4") (pin "2") (pinfunction "2_2") (pintype "passive"))
      (node (ref "R8") (pin "2") (pinfunction "2_2") (pintype "passive"))
      (node (ref "R9") (pin "2") (pinfunction "2_2") (pintype "passive"))
    )
    (net (code "4") (name "+4.3V") (class "Default")
      (node (ref "4V3") (pin "TP") (pinfunction "TP_TP") (pintype "input"))
      (node (ref "C11") (pin "1") (pinfunction "1_1") (pintype "passive"))
      (node (ref "C12") (pin "1") (pinfunction "1_1") (pintype "passive"))
      (node (ref "C13") (pin "1") (pinfunction "1_1") (pintype "passive"))
      (node (ref "C14") (pin "1") (pinfunction "1_1") (pintype "passive"))
      (node (ref "C21") (pin "1") (pinfunction "1_1") (pintype "passive"))
      (node (ref "C22") (pin "1") (pinfunction "1_1") (pintype "passive"))
      (node (ref "C23") (pin "1") (pinfunction "1_1") (pintype "passive"))
      (node (ref "C24") (pin "1") (pinfunction "1_1") (pintype "passive"))
      (node (ref "C31") (pin "1") (pinfunction "1_1") (pintype "passive"))
      (node (ref "C32") (pin "1") (pinfunction "1_1") (pintype "passive"))
      (node (ref "C33") (pin "1") (pinfunction "1_1") (pintype "passive"))
      (node (ref "C34") (pin "1") (pinfunction "1_1") (pintype "passive"))
      (node (ref "IC1") (pin "18") (pinfunction "VCC_18") (pintype "power_in"))
      (node (ref "IC1") (pin "31") (pinfunction "VCC_31") (pintype "power_in"))
      (node (ref "IC1") (pin "42") (pinfunction "VCC_42") (pintype "power_in"))
      (node (ref "IC1") (pin "7") (pinfunction "VCC_7") (pintype "power_in"))
      (node (ref "IC2") (pin "18") (pinfunction "VCC_18") (pintype "power_in"))
      (node (ref "IC2") (pin "31") (pinfunction "VCC_31") (pintype "power_in"))
      (node (ref "IC2") (pin "42") (pinfunction "VCC_42") (pintype "power_in"))
      (node (ref "IC2") (pin "7") (pinfunction "VCC_7") (pintype "power_in"))
      (node (ref "IC3") (pin "18") (pinfunction "VCC_18") (pintype "power_in"))
      (node (ref "IC3") (pin "31") (pinfunction "VCC_31") (pintype "power_in"))
      (node (ref "IC3") (pin "42") (pinfunction "VCC_42") (pintype "power_in"))
      (node (ref "IC3") (pin "7") (pinfunction "VCC_7") (pintype "power_in"))
      (node (ref "IC9") (pin "5") (pinfunction "OUT_5") (pintype "passive"))
    )
    (net (code "5") (name "+5V") (class "Default")
      (node (ref "5V") (pin "TP") (pinfunction "TP_TP") (pintype "input"))
      (node (ref "C10") (pin "1") (pinfunction "1_1") (pintype "passive"))
      (node (ref "C15") (pin "1") (pinfunction "1_1") (pintype "passive"))
      (node (ref "C16") (pin "1") (pinfunction "1_1") (pintype "passive"))
      (node (ref "C17") (pin "1") (pinfunction "1_1") (pintype "passive"))
      (node (ref "C2") (pin "1") (pinfunction "1_1") (pintype "passive"))
      (node (ref "C3") (pin "2") (pinfunction "2_2") (pintype "passive"))
      (node (ref "C9") (pin "1") (pinfunction "1_1") (pintype "passive"))
      (node (ref "CN1") (pin "1") (pinfunction "VCC_1") (pintype "bidirectional"))
      (node (ref "CN1") (pin "2") (pinfunction "VCC_2") (pintype "bidirectional"))
      (node (ref "CN1") (pin "40") (pinfunction "~{BOE}_40") (pintype "bidirectional"))
      (node (ref "CN1") (pin "76") (pinfunction "VCC_76") (pintype "bidirectional"))
      (node (ref "CN2") (pin "2") (pinfunction "5V_2") (pintype "power_in"))
      (node (ref "CN2") (pin "4") (pinfunction "5V_4") (pintype "power_in"))
      (node (ref "IC7") (pin "3") (pinfunction "VIN_3") (pintype "power_in"))
      (node (ref "IC7") (pin "5") (pinfunction "EN_5") (pintype "input"))
      (node (ref "IC9") (pin "1") (pinfunction "IN_1") (pintype "input"))
      (node (ref "IC9") (pin "3") (pinfunction "~{EN}_3") (pintype "input"))
      (node (ref "R24") (pin "2") (pinfunction "2_2") (pintype "passive"))
      (node (ref "R27") (pin "2") (pinfunction "2_2") (pintype "passive"))
      (node (ref "T1") (pin "E") (pinfunction "E_E") (pintype "passive"))
      (node (ref "T4") (pin "E") (pinfunction "E_E") (pintype "passive"))
    )
    (net (code "12") (name "3VA0") (class "Default")
      (node (ref "IC2") (pin "26") (pinfunction "A4_26") (pintype "bidirectional"))
      (node (ref "IC5") (pin "25") (pinfunction "GPIO25_25") (pintype "bidirectional"))
    )
    (net (code "13") (name "3VA1") (class "Default")
      (node (ref "IC2") (pin "27") (pinfunction "A3_27") (pintype "bidirectional"))
      (node (ref "IC5") (pin "24") (pinfunction "GPIO24_24") (pintype "bidirectional"))
    )
    (net (code "14") (name "3VA2") (class "Default")
      (node (ref "IC2") (pin "29") (pinfunction "A2_29") (pintype "bidirectional"))
      (node (ref "IC5") (pin "22") (pinfunction "GPIO22_22") (pintype "bidirectional"))
    )
    (net (code "15") (name "3VA3") (class "Default")
      (node (ref "IC2") (pin "30") (pinfunction "A1_30") (pintype "bidirectional"))
      (node (ref "IC5") (pin "21") (pinfunction "GPIO21_21") (pintype "bidirectional"))
    )
    (net (code "16") (name "3VA4") (class "Default")
      (node (ref "IC2") (pin "32") (pinfunction "A4_32") (pintype "bidirectional"))
      (node (ref "IC5") (pin "17") (pinfunction "GPIO17/VREFB1N0_17") (pintype "bidirectional"))
    )
    (net (code "17") (name "3VA5") (class "Default")
      (node (ref "IC2") (pin "33") (pinfunction "A3_33") (pintype "bidirectional"))
      (node (ref "IC5") (pin "15") (pinfunction "GPIO15/JTAGEN_15") (pintype "bidirectional"))
    )
    (net (code "18") (name "3VA6") (class "Default")
      (node (ref "IC2") (pin "35") (pinfunction "A2_35") (pintype "bidirectional"))
      (node (ref "IC5") (pin "14") (pinfunction "GPIO14_14") (pintype "bidirectional"))
    )
    (net (code "19") (name "3VA7") (class "Default")
      (node (ref "IC2") (pin "36") (pinfunction "A1_36") (pintype "bidirectional"))
      (node (ref "IC5") (pin "13") (pinfunction "GPIO13_13") (pintype "bidirectional"))
    )
    (net (code "20") (name "3VA8") (class "Default")
      (node (ref "IC2") (pin "37") (pinfunction "A4_37") (pintype "bidirectional"))
      (node (ref "IC5") (pin "12") (pinfunction "GPIO12_12") (pintype "bidirectional"))
    )
    (net (code "21") (name "3VA9") (class "Default")
      (node (ref "IC2") (pin "38") (pinfunction "A3_38") (pintype "bidirectional"))
      (node (ref "IC5") (pin "11") (pinfunction "GPIO11_11") (pintype "bidirectional"))
    )
    (net (code "22") (name "3VCASL0") (class "Default")
      (node (ref "IC2") (pin "41") (pinfunction "A1_41") (pintype "bidirectional"))
      (node (ref "IC5") (pin "8") (pinfunction "GPIO8_8") (pintype "bidirectional"))
    )
    (net (code "23") (name "3VCASL1") (class "Default")
      (node (ref "IC2") (pin "43") (pinfunction "A4_43") (pintype "bidirectional"))
      (node (ref "IC5") (pin "7") (pinfunction "GPIO7_7") (pintype "bidirectional"))
    )
    (net (code "24") (name "3VCASU0") (class "Default")
      (node (ref "IC2") (pin "40") (pinfunction "A2_40") (pintype "bidirectional"))
      (node (ref "IC5") (pin "10") (pinfunction "GPIO10_10") (pintype "bidirectional"))
    )
    (net (code "25") (name "3VCASU1") (class "Default")
      (node (ref "IC2") (pin "44") (pinfunction "A3_44") (pintype "bidirectional"))
      (node (ref "IC5") (pin "6") (pinfunction "GPIO6_6") (pintype "bidirectional"))
    )
    (net (code "26") (name "3VCCK") (class "Default")
      (node (ref "IC1") (pin "47") (pinfunction "A1_47") (pintype "bidirectional"))
      (node (ref "IC8") (pin "1") (pinfunction "X1/CLK_1") (pintype "input"))
    )
    (net (code "27") (name "3VCPA2") (class "Default")
      (node (ref "IC1") (pin "33") (pinfunction "A3_33") (pintype "bidirectional"))
      (node (ref "IC5") (pin "131") (pinfunction "GPIO131_131") (pintype "bidirectional"))
    )
    (net (code "28") (name "3VCPA3") (class "Default")
      (node (ref "IC1") (pin "35") (pinfunction "A2_35") (pintype "bidirectional"))
      (node (ref "IC5") (pin "130") (pinfunction "GPIO130_130") (pintype "bidirectional"))
    )
    (net (code "29") (name "3VCPA4") (class "Default")
      (node (ref "IC1") (pin "36") (pinfunction "A1_36") (pintype "bidirectional"))
      (node (ref "IC5") (pin "129") (pinfunction "GPI129/~{CONFIG}_129") (pintype "input"))
    )
    (net (code "30") (name "3VCPA5") (class "Default")
      (node (ref "IC1") (pin "37") (pinfunction "A4_37") (pintype "bidirectional"))
      (node (ref "IC5") (pin "127") (pinfunction "GPIO127_127") (pintype "bidirectional"))
    )
    (net (code "31") (name "3VCPD0") (class "Default")
      (node (ref "IC1") (pin "27") (pinfunction "A3_27") (pintype "bidirectional"))
      (node (ref "IC5") (pin "136") (pinfunction "GPIO136/~{STATUS}_136") (pintype "bidirectional"))
    )
    (net (code "32") (name "3VCPD1") (class "Default")
      (node (ref "IC1") (pin "29") (pinfunction "A2_29") (pintype "bidirectional"))
      (node (ref "IC5") (pin "135") (pinfunction "GPIO135_135") (pintype "bidirectional"))
    )
    (net (code "33") (name "3VCPD2") (class "Default")
      (node (ref "IC1") (pin "30") (pinfunction "A1_30") (pintype "bidirectional"))
      (node (ref "IC5") (pin "134") (pinfunction "GPIO134/CRC_ERROR_134") (pintype "bidirectional"))
    )
    (net (code "34") (name "3VCPD3") (class "Default")
      (node (ref "IC1") (pin "32") (pinfunction "A4_32") (pintype "bidirectional"))
      (node (ref "IC5") (pin "132") (pinfunction "GPIO132_132") (pintype "bidirectional"))
    )
    (net (code "35") (name "3VD0") (class "Default")
      (node (ref "IC3") (pin "26") (pinfunction "A4_26") (pintype "bidirectional"))
      (node (ref "IC5") (pin "54") (pinfunction "GPIO54_54") (pintype "bidirectional"))
    )
    (net (code "36") (name "3VD1") (class "Default")
      (node (ref "IC3") (pin "27") (pinfunction "A3_27") (pintype "bidirectional"))
      (node (ref "IC5") (pin "52") (pinfunction "GPIO52_52") (pintype "bidirectional"))
    )
    (net (code "37") (name "3VD2") (class "Default")
      (node (ref "IC3") (pin "29") (pinfunction "A2_29") (pintype "bidirectional"))
      (node (ref "IC5") (pin "50") (pinfunction "GPIO50_50") (pintype "bidirectional"))
    )
    (net (code "38") (name "3VD3") (class "Default")
      (node (ref "IC3") (pin "30") (pinfunction "A1_30") (pintype "bidirectional"))
      (node (ref "IC5") (pin "48") (pinfunction "GPIO48/VREFB3N0_48") (pintype "bidirectional"))
    )
    (net (code "39") (name "3VD4") (class "Default")
      (node (ref "IC3") (pin "32") (pinfunction "A4_32") (pintype "bidirectional"))
      (node (ref "IC5") (pin "47") (pinfunction "GPIO47_47") (pintype "bidirectional"))
    )
    (net (code "40") (name "3VD5") (class "Default")
      (node (ref "IC3") (pin "33") (pinfunction "A3_33") (pintype "bidirectional"))
      (node (ref "IC5") (pin "46") (pinfunction "GPIO46_46") (pintype "bidirectional"))
    )
    (net (code "41") (name "3VD6") (class "Default")
      (node (ref "IC3") (pin "35") (pinfunction "A2_35") (pintype "bidirectional"))
      (node (ref "IC5") (pin "45") (pinfunction "GPIO45_45") (pintype "bidirectional"))
    )
    (net (code "42") (name "3VD7") (class "Default")
      (node (ref "IC3") (pin "36") (pinfunction "A1_36") (pintype "bidirectional"))
      (node (ref "IC5") (pin "44") (pinfunction "GPIO44_44") (pintype "bidirectional"))
    )
    (net (code "43") (name "3VD8") (class "Default")
      (node (ref "IC3") (pin "37") (pinfunction "A4_37") (pintype "bidirectional"))
      (node (ref "IC5") (pin "43") (pinfunction "GPIO43_43") (pintype "bidirectional"))
    )
    (net (code "44") (name "3VD9") (class "Default")
      (node (ref "IC3") (pin "38") (pinfunction "A3_38") (pintype "bidirectional"))
      (node (ref "IC5") (pin "41") (pinfunction "GPIO41_41") (pintype "bidirectional"))
    )
    (net (code "45") (name "3VD10") (class "Default")
      (node (ref "IC3") (pin "40") (pinfunction "A2_40") (pintype "bidirectional"))
      (node (ref "IC5") (pin "39") (pinfunction "GPIO39_39") (pintype "bidirectional"))
    )
    (net (code "46") (name "3VD11") (class "Default")
      (node (ref "IC3") (pin "41") (pinfunction "A1_41") (pintype "bidirectional"))
      (node (ref "IC5") (pin "38") (pinfunction "GPIO38_38") (pintype "bidirectional"))
    )
    (net (code "47") (name "3VD12") (class "Default")
      (node (ref "IC3") (pin "43") (pinfunction "A4_43") (pintype "bidirectional"))
      (node (ref "IC5") (pin "33") (pinfunction "GPIO33/PLL_L_CLKOUTP_33") (pintype "bidirectional"))
    )
    (net (code "48") (name "3VD13") (class "Default")
      (node (ref "IC3") (pin "44") (pinfunction "A3_44") (pintype "bidirectional"))
      (node (ref "IC5") (pin "32") (pinfunction "GPIO32/PLL_L_CLKOUTN_32") (pintype "bidirectional"))
    )
    (net (code "49") (name "3VD14") (class "Default")
      (node (ref "IC3") (pin "46") (pinfunction "A2_46") (pintype "bidirectional"))
      (node (ref "IC5") (pin "30") (pinfunction "GPIO30/VREFB2N0_30") (pintype "bidirectional"))
    )
    (net (code "50") (name "3VD15") (class "Default")
      (node (ref "IC3") (pin "47") (pinfunction "A1_47") (pintype "bidirectional"))
      (node (ref "IC5") (pin "29") (pinfunction "GPIO29/CLK1P_29") (pintype "bidirectional"))
    )
    (net (code "51") (name "3VINT2") (class "Default")
      (node (ref "IC1") (pin "38") (pinfunction "A3_38") (pintype "bidirectional"))
      (node (ref "IC5") (pin "124") (pinfunction "GPIO124_124") (pintype "bidirectional"))
    )
    (net (code "52") (name "3VIORD") (class "Default")
      (node (ref "IC1") (pin "41") (pinfunction "A1_41") (pintype "bidirectional"))
      (node (ref "IC5") (pin "122") (pinfunction "GPIO122/DEV_OE_122") (pintype "bidirectional"))
    )
    (net (code "53") (name "3VIOWR") (class "Default")
      (node (ref "IC1") (pin "43") (pinfunction "A4_43") (pintype "bidirectional"))
      (node (ref "IC5") (pin "121") (pinfunction "GPIO121/~{DEV_CLR}_121") (pintype "bidirectional"))
    )
    (net (code "54") (name "3VRAS0") (class "Default")
      (node (ref "IC2") (pin "46") (pinfunction "A2_46") (pintype "bidirectional"))
      (node (ref "IC5") (pin "141") (pinfunction "GPIO141_141") (pintype "bidirectional"))
    )
    (net (code "55") (name "3VRAS1") (class "Default")
      (node (ref "IC2") (pin "47") (pinfunction "A1_47") (pintype "bidirectional"))
      (node (ref "IC5") (pin "140") (pinfunction "GPIO140_140") (pintype "bidirectional"))
    )
    (net (code "56") (name "3VRTCCS") (class "Default")
      (node (ref "IC1") (pin "40") (pinfunction "A2_40") (pintype "bidirectional"))
      (node (ref "IC5") (pin "123") (pinfunction "GPIO123/VREFB8N0_123") (pintype "bidirectional"))
    )
    (net (code "57") (name "3VWE") (class "Default")
      (node (ref "IC1") (pin "26") (pinfunction "A4_26") (pintype "bidirectional"))
      (node (ref "IC5") (pin "138") (pinfunction "GPIO138/CONF_DONE_138") (pintype "bidirectional"))
    )
    (net (code "58") (name "A2") (class "Default")
      (node (ref "CN1") (pin "57") (pinfunction "A2_57") (pintype "bidirectional"))
      (node (ref "IC1") (pin "16") (pinfunction "B3_16") (pintype "bidirectional"))
    )
    (net (code "59") (name "A3") (class "Default")
      (node (ref "CN1") (pin "58") (pinfunction "A3_58") (pintype "bidirectional"))
      (node (ref "IC1") (pin "14") (pinfunction "B2_14") (pintype "bidirectional"))
    )
    (net (code "60") (name "A4") (class "Default")
      (node (ref "CN1") (pin "59") (pinfunction "A4_59") (pintype "bidirectional"))
      (node (ref "IC1") (pin "13") (pinfunction "B1_13") (pintype "bidirectional"))
    )
    (net (code "61") (name "A5") (class "Default")
      (node (ref "CN1") (pin "60") (pinfunction "A5_60") (pintype "bidirectional"))
      (node (ref "IC1") (pin "12") (pinfunction "B4_12") (pintype "bidirectional"))
    )
    (net (code "62") (name "A314") (class "Default")
      (node (ref "CN7") (pin "5") (pinfunction "S_5") (pintype "passive"))
      (node (ref "R22") (pin "1") (pinfunction "1_1") (pintype "passive"))
    )
    (net (code "63") (name "A_A314") (class "Default")
      (node (ref "CN3") (pin "1") (pinfunction "S_1") (pintype "passive"))
      (node (ref "T1") (pin "C") (pinfunction "C_C") (pintype "passive"))
    )
    (net (code "64") (name "A_FD") (class "Default")
      (node (ref "CN3") (pin "3") (pinfunction "S_3") (pintype "passive"))
      (node (ref "CN4") (pin "3") (pinfunction "3_3") (pintype "passive"))
      (node (ref "CN5") (pin "3") (pinfunction "3_3") (pintype "passive"))
    )
    (net (code "65") (name "A_HD") (class "Default")
      (node (ref "CN3") (pin "2") (pinfunction "S_2") (pintype "passive"))
      (node (ref "CN5") (pin "4") (pinfunction "4_4") (pintype "passive"))
      (node (ref "R28") (pin "2") (pinfunction "2_2") (pintype "passive"))
    )
    (net (code "66") (name "A_PW") (class "Default")
      (node (ref "CN3") (pin "4") (pinfunction "S_4") (pintype "passive"))
      (node (ref "CN4") (pin "2") (pinfunction "2_2") (pintype "passive"))
      (node (ref "CN5") (pin "2") (pinfunction "2_2") (pintype "passive"))
    )
    (net (code "67") (name "BCASL0") (class "Default")
      (node (ref "CN1") (pin "34") (pinfunction "~{BCASL0}_34") (pintype "bidirectional"))
      (node (ref "R12") (pin "1") (pinfunction "P$1_1") (pintype "passive"))
    )
    (net (code "68") (name "BCASL1") (class "Default")
      (node (ref "CN1") (pin "35") (pinfunction "~{BCASL1}_35") (pintype "bidirectional"))
      (node (ref "R11") (pin "4") (pinfunction "P$1_4") (pintype "passive"))
    )
    (net (code "69") (name "BCASU0") (class "Default")
      (node (ref "CN1") (pin "33") (pinfunction "~{BCASU0}_33") (pintype "bidirectional"))
      (node (ref "R12") (pin "2") (pinfunction "P$1_2") (pintype "passive"))
    )
    (net (code "70") (name "BCASU1") (class "Default")
      (node (ref "CN1") (pin "36") (pinfunction "~{BCASU1}_36") (pintype "bidirectional"))
      (node (ref "R11") (pin "3") (pinfunction "P$1_3") (pintype "passive"))
    )
    (net (code "71") (name "BRAS0") (class "Default")
      (node (ref "CN1") (pin "37") (pinfunction "~{BRAS0}_37") (pintype "bidirectional"))
      (node (ref "R11") (pin "2") (pinfunction "P$1_2") (pintype "passive"))
    )
    (net (code "72") (name "BRAS1") (class "Default")
      (node (ref "CN1") (pin "38") (pinfunction "~{BRAS1}_38") (pintype "bidirectional"))
      (node (ref "R11") (pin "1") (pinfunction "P$1_1") (pintype "passive"))
    )
    (net (code "73") (name "BWE") (class "Default")
      (node (ref "CN1") (pin "39") (pinfunction "~{BWE}_39") (pintype "bidirectional"))
      (node (ref "R5") (pin "1") (pinfunction "1_1") (pintype "passive"))
    )
    (net (code "74") (name "CCK") (class "Default")
      (node (ref "CN1") (pin "69") (pinfunction "CCK_69") (pintype "bidirectional"))
      (node (ref "IC1") (pin "2") (pinfunction "B1_2") (pintype "bidirectional"))
    )
    (net (code "75") (name "D0") (class "Default")
      (node (ref "CN1") (pin "49") (pinfunction "D0_49") (pintype "bidirectional"))
      (node (ref "IC1") (pin "22") (pinfunction "B3_22") (pintype "bidirectional"))
    )
    (net (code "76") (name "D1") (class "Default")
      (node (ref "CN1") (pin "50") (pinfunction "D1_50") (pintype "bidirectional"))
      (node (ref "IC1") (pin "20") (pinfunction "B2_20") (pintype "bidirectional"))
    )
    (net (code "77") (name "D2") (class "Default")
      (node (ref "CN1") (pin "51") (pinfunction "D2_51") (pintype "bidirectional"))
      (node (ref "IC1") (pin "19") (pinfunction "B1_19") (pintype "bidirectional"))
    )
    (net (code "78") (name "D3") (class "Default")
      (node (ref "CN1") (pin "52") (pinfunction "D3_52") (pintype "bidirectional"))
      (node (ref "IC1") (pin "17") (pinfunction "B4_17") (pintype "bidirectional"))
    )
    (net (code "79") (name "DRA0") (class "Default")
      (node (ref "CN1") (pin "23") (pinfunction "BDRA0_23") (pintype "bidirectional"))
      (node (ref "R14") (pin "4") (pinfunction "P$1_4") (pintype "passive"))
    )
    (net (code "80") (name "DRA1") (class "Default")
      (node (ref "CN1") (pin "24") (pinfunction "BDRA1_24") (pintype "bidirectional"))
      (node (ref "R14") (pin "3") (pinfunction "P$1_3") (pintype "passive"))
    )
    (net (code "81") (name "DRA2") (class "Default")
      (node (ref "CN1") (pin "25") (pinfunction "BDRA2_25") (pintype "bidirectional"))
      (node (ref "R14") (pin "2") (pinfunction "P$1_2") (pintype "passive"))
    )
    (net (code "82") (name "DRA3") (class "Default")
      (node (ref "CN1") (pin "26") (pinfunction "BDRA3_26") (pintype "bidirectional"))
      (node (ref "R14") (pin "1") (pinfunction "P$1_1") (pintype "passive"))
    )
    (net (code "83") (name "DRA4") (class "Default")
      (node (ref "CN1") (pin "27") (pinfunction "BDRA4_27") (pintype "bidirectional"))
      (node (ref "R13") (pin "4") (pinfunction "P$1_4") (pintype "passive"))
    )
    (net (code "84") (name "DRA5") (class "Default")
      (node (ref "CN1") (pin "28") (pinfunction "BDRA5_28") (pintype "bidirectional"))
      (node (ref "R13") (pin "3") (pinfunction "P$1_3") (pintype "passive"))
    )
    (net (code "85") (name "DRA6") (class "Default")
      (node (ref "CN1") (pin "29") (pinfunction "BDRA6_29") (pintype "bidirectional"))
      (node (ref "R13") (pin "2") (pinfunction "P$1_2") (pintype "passive"))
    )
    (net (code "86") (name "DRA7") (class "Default")
      (node (ref "CN1") (pin "30") (pinfunction "BDRA7_30") (pintype "bidirectional"))
      (node (ref "R13") (pin "1") (pinfunction "P$1_1") (pintype "passive"))
    )
    (net (code "87") (name "DRA8") (class "Default")
      (node (ref "CN1") (pin "31") (pinfunction "BDRA8_31") (pintype "bidirectional"))
      (node (ref "R12") (pin "4") (pinfunction "P$1_4") (pintype "passive"))
    )
    (net (code "88") (name "DRA9") (class "Default")
      (node (ref "CN1") (pin "32") (pinfunction "BDRA9_32") (pintype "bidirectional"))
      (node (ref "R12") (pin "3") (pinfunction "P$1_3") (pintype "passive"))
    )
    (net (code "89") (name "DRD0") (class "Default")
      (node (ref "CN1") (pin "5") (pinfunction "DRD0_5") (pintype "bidirectional"))
      (node (ref "IC3") (pin "23") (pinfunction "B4_23") (pintype "bidirectional"))
    )
    (net (code "90") (name "DRD1") (class "Default")
      (node (ref "CN1") (pin "6") (pinfunction "DRD1_6") (pintype "bidirectional"))
      (node (ref "IC3") (pin "22") (pinfunction "B3_22") (pintype "bidirectional"))
    )
    (net (code "91") (name "DRD2") (class "Default")
      (node (ref "CN1") (pin "7") (pinfunction "DRD2_7") (pintype "bidirectional"))
      (node (ref "IC3") (pin "20") (pinfunction "B2_20") (pintype "bidirectional"))
    )
    (net (code "92") (name "DRD3") (class "Default")
      (node (ref "CN1") (pin "8") (pinfunction "DRD3_8") (pintype "bidirectional"))
      (node (ref "IC3") (pin "19") (pinfunction "B1_19") (pintype "bidirectional"))
    )
    (net (code "93") (name "DRD4") (class "Default")
      (node (ref "CN1") (pin "9") (pinfunction "DRD4_9") (pintype "bidirectional"))
      (node (ref "IC3") (pin "17") (pinfunction "B4_17") (pintype "bidirectional"))
    )
    (net (code "94") (name "DRD5") (class "Default")
      (node (ref "CN1") (pin "10") (pinfunction "DRD5_10") (pintype "bidirectional"))
      (node (ref "IC3") (pin "16") (pinfunction "B3_16") (pintype "bidirectional"))
    )
    (net (code "95") (name "DRD6") (class "Default")
      (node (ref "CN1") (pin "11") (pinfunction "DRD6_11") (pintype "bidirectional"))
      (node (ref "IC3") (pin "14") (pinfunction "B2_14") (pintype "bidirectional"))
    )
    (net (code "96") (name "DRD7") (class "Default")
      (node (ref "CN1") (pin "12") (pinfunction "DRD7_12") (pintype "bidirectional"))
      (node (ref "IC3") (pin "13") (pinfunction "B1_13") (pintype "bidirectional"))
    )
    (net (code "97") (name "DRD8") (class "Default")
      (node (ref "CN1") (pin "13") (pinfunction "DRD8_13") (pintype "bidirectional"))
      (node (ref "IC3") (pin "12") (pinfunction "B4_12") (pintype "bidirectional"))
    )
    (net (code "98") (name "DRD9") (class "Default")
      (node (ref "CN1") (pin "14") (pinfunction "DRD9_14") (pintype "bidirectional"))
      (node (ref "IC3") (pin "11") (pinfunction "B3_11") (pintype "bidirectional"))
    )
    (net (code "99") (name "DRD10") (class "Default")
      (node (ref "CN1") (pin "15") (pinfunction "DRD10_15") (pintype "bidirectional"))
      (node (ref "IC3") (pin "9") (pinfunction "B2_9") (pintype "bidirectional"))
    )
    (net (code "100") (name "DRD11") (class "Default")
      (node (ref "CN1") (pin "16") (pinfunction "DRD11_16") (pintype "bidirectional"))
      (node (ref "IC3") (pin "8") (pinfunction "B1_8") (pintype "bidirectional"))
    )
    (net (code "101") (name "DRD12") (class "Default")
      (node (ref "CN1") (pin "17") (pinfunction "DRD12_17") (pintype "bidirectional"))
      (node (ref "IC3") (pin "6") (pinfunction "B4_6") (pintype "bidirectional"))
    )
    (net (code "102") (name "DRD13") (class "Default")
      (node (ref "CN1") (pin "18") (pinfunction "DRD13_18") (pintype "bidirectional"))
      (node (ref "IC3") (pin "5") (pinfunction "B3_5") (pintype "bidirectional"))
    )
    (net (code "103") (name "DRD14") (class "Default")
      (node (ref "CN1") (pin "19") (pinfunction "DRD14_19") (pintype "bidirectional"))
      (node (ref "IC3") (pin "3") (pinfunction "B2_3") (pintype "bidirectional"))
    )
    (net (code "104") (name "DRD15") (class "Default")
      (node (ref "CN1") (pin "20") (pinfunction "DRD15_20") (pintype "bidirectional"))
      (node (ref "IC3") (pin "2") (pinfunction "B1_2") (pintype "bidirectional"))
    )
    (net (code "105") (name "FD") (class "Default")
      (node (ref "CN7") (pin "3") (pinfunction "S_3") (pintype "passive"))
      (node (ref "R15") (pin "1") (pinfunction "1_1") (pintype "passive"))
    )
    (net (code "106") (name "GND") (class "Default")
      (node (ref "BAT1") (pin "GND") (pinfunction "-_GND") (pintype "power_in"))
      (node (ref "C1") (pin "2") (pinfunction "2_2") (pintype "passive"))
      (node (ref "C10") (pin "2") (pinfunction "2_2") (pintype "passive"))
      (node (ref "C11") (pin "2") (pinfunction "2_2") (pintype "passive"))
      (node (ref "C12") (pin "2") (pinfunction "2_2") (pintype "passive"))
      (node (ref "C13") (pin "2") (pinfunction "2_2") (pintype "passive"))
      (node (ref "C14") (pin "2") (pinfunction "2_2") (pintype "passive"))
      (node (ref "C15") (pin "2") (pinfunction "2_2") (pintype "passive"))
      (node (ref "C16") (pin "2") (pinfunction "2_2") (pintype "passive"))
      (node (ref "C17") (pin "2") (pinfunction "2_2") (pintype "passive"))
      (node (ref "C2") (pin "2") (pinfunction "2_2") (pintype "passive"))
      (node (ref "C21") (pin "2") (pinfunction "2_2") (pintype "passive"))
      (node (ref "C22") (pin "2") (pinfunction "2_2") (pintype "passive"))
      (node (ref "C23") (pin "2") (pinfunction "2_2") (pintype "passive"))
      (node (ref "C24") (pin "2") (pinfunction "2_2") (pintype "passive"))
      (node (ref "C3") (pin "1") (pinfunction "1_1") (pintype "passive"))
      (node (ref "C31") (pin "2") (pinfunction "2_2") (pintype "passive"))
      (node (ref "C32") (pin "2") (pinfunction "2_2") (pintype "passive"))
      (node (ref "C33") (pin "2") (pinfunction "2_2") (pintype "passive"))
      (node (ref "C34") (pin "2") (pinfunction "2_2") (pintype "passive"))
      (node (ref "C41") (pin "2") (pinfunction "2_2") (pintype "passive"))
      (node (ref "C42") (pin "2") (pinfunction "2_2") (pintype "passive"))
      (node (ref "C5") (pin "2") (pinfunction "2_2") (pintype "passive"))
      (node (ref "C50") (pin "2") (pinfunction "2_2") (pintype "passive"))
      (node (ref "C51") (pin "2") (pinfunction "2_2") (pintype "passive"))
      (node (ref "C52") (pin "2") (pinfunction "2_2") (pintype "passive"))
      (node (ref "C53") (pin "2") (pinfunction "2_2") (pintype "passive"))
      (node (ref "C54") (pin "2") (pinfunction "2_2") (pintype "passive"))
      (node (ref "C55") (pin "2") (pinfunction "2_2") (pintype "passive"))
      (node (ref "C56") (pin "2") (pinfunction "2_2") (pintype "passive"))
      (node (ref "C57") (pin "2") (pinfunction "2_2") (pintype "passive"))
      (node (ref "C58") (pin "2") (pinfunction "2_2") (pintype "passive"))
      (node (ref "C59") (pin "2") (pinfunction "2_2") (pintype "passive"))
      (node (ref "C6") (pin "2") (pinfunction "2_2") (pintype "passive"))
      (node (ref "C60") (pin "2") (pinfunction "2_2") (pintype "passive"))
      (node (ref "C61") (pin "2") (pinfunction "2_2") (pintype "passive"))
      (node (ref "C62") (pin "2") (pinfunction "2_2") (pintype "passive"))
      (node (ref "C63") (pin "2") (pinfunction "2_2") (pintype "passive"))
      (node (ref "C64") (pin "2") (pinfunction "2_2") (pintype "passive"))
      (node (ref "C65") (pin "2") (pinfunction "2_2") (pintype "passive"))
      (node (ref "C66") (pin "2") (pinfunction "2_2") (pintype "passive"))
      (node (ref "C67") (pin "2") (pinfunction "2_2") (pintype "passive"))
      (node (ref "C68") (pin "2") (pinfunction "2_2") (pintype "passive"))
      (node (ref "C69") (pin "2") (pinfunction "2_2") (pintype "passive"))
      (node (ref "C7") (pin "2") (pinfunction "2_2") (pintype "passive"))
      (node (ref "C70") (pin "2") (pinfunction "2_2") (pintype "passive"))
      (node (ref "C71") (pin "2") (pinfunction "2_2") (pintype "passive"))
      (node (ref "C72") (pin "2") (pinfunction "2_2") (pintype "passive"))
      (node (ref "C8") (pin "2") (pinfunction "2_2") (pintype "passive"))
      (node (ref "C9") (pin "2") (pinfunction "2_2") (pintype "passive"))
      (node (ref "CN1") (pin "21") (pinfunction "GND_21") (pintype "bidirectional"))
      (node (ref "CN1") (pin "22") (pinfunction "GND_22") (pintype "bidirectional"))
      (node (ref "CN1") (pin "3") (pinfunction "GND_3") (pintype "bidirectional"))
      (node (ref "CN1") (pin "4") (pinfunction "GND_4") (pintype "bidirectional"))
      (node (ref "CN1") (pin "77") (pinfunction "GND_77") (pintype "bidirectional"))
      (node (ref "CN1") (pin "78") (pinfunction "GND_78") (pintype "bidirectional"))
      (node (ref "CN2") (pin "14") (pinfunction "GND_14") (pintype "power_in"))
      (node (ref "CN2") (pin "20") (pinfunction "GND_20") (pintype "power_in"))
      (node (ref "CN2") (pin "25") (pinfunction "GND_25") (pintype "power_in"))
      (node (ref "CN2") (pin "30") (pinfunction "GND_30") (pintype "power_in"))
      (node (ref "CN2") (pin "34") (pinfunction "GND_34") (pintype "power_in"))
      (node (ref "CN2") (pin "39") (pinfunction "GND_39") (pintype "power_in"))
      (node (ref "CN2") (pin "6") (pinfunction "GND_6") (pintype "power_in"))
      (node (ref "CN2") (pin "9") (pinfunction "GND_9") (pintype "power_in"))
      (node (ref "CN3") (pin "5") (pinfunction "S_5") (pintype "passive"))
      (node (ref "CN4") (pin "1") (pinfunction "1_1") (pintype "passive"))
      (node (ref "CN5") (pin "1") (pinfunction "1_1") (pintype "passive"))
      (node (ref "CN6") (pin "1") (pinfunction "1_1") (pintype "passive"))
      (node (ref "CN7") (pin "1") (pinfunction "S_1") (pintype "passive"))
      (node (ref "GND") (pin "TP") (pinfunction "TP_TP") (pintype "input"))
      (node (ref "IC1") (pin "1") (pinfunction "~{OE}_1") (pintype "input"))
      (node (ref "IC1") (pin "10") (pinfunction "GND_10") (pintype "power_in"))
      (node (ref "IC1") (pin "15") (pinfunction "GND_15") (pintype "power_in"))
      (node (ref "IC1") (pin "21") (pinfunction "GND_21") (pintype "power_in"))
      (node (ref "IC1") (pin "24") (pinfunction "~{OE}_24") (pintype "input"))
      (node (ref "IC1") (pin "25") (pinfunction "~{OE}_25") (pintype "input"))
      (node (ref "IC1") (pin "28") (pinfunction "GND_28") (pintype "power_in"))
      (node (ref "IC1") (pin "3") (pinfunction "B2_3") (pintype "bidirectional"))
      (node (ref "IC1") (pin "34") (pinfunction "GND_34") (pintype "power_in"))
      (node (ref "IC1") (pin "39") (pinfunction "GND_39") (pintype "power_in"))
      (node (ref "IC1") (pin "4") (pinfunction "GND_4") (pintype "power_in"))
      (node (ref "IC1") (pin "45") (pinfunction "GND_45") (pintype "power_in"))
      (node (ref "IC1") (pin "48") (pinfunction "~{OE}_48") (pintype "input"))
      (node (ref "IC1") (pin "5") (pinfunction "B3_5") (pintype "bidirectional"))
      (node (ref "IC10") (pin "1") (pinfunction "A0_1") (pintype "input"))
      (node (ref "IC10") (pin "2") (pinfunction "A1_2") (pintype "input"))
      (node (ref "IC10") (pin "3") (pinfunction "A2_3") (pintype "input"))
      (node (ref "IC10") (pin "4") (pinfunction "GND_4") (pintype "power_in"))
      (node (ref "IC2") (pin "1") (pinfunction "~{OE}_1") (pintype "input"))
      (node (ref "IC2") (pin "10") (pinfunction "GND_10") (pintype "power_in"))
      (node (ref "IC2") (pin "15") (pinfunction "GND_15") (pintype "power_in"))
      (node (ref "IC2") (pin "21") (pinfunction "GND_21") (pintype "power_in"))
      (node (ref "IC2") (pin "24") (pinfunction "~{OE}_24") (pintype "input"))
      (node (ref "IC2") (pin "25") (pinfunction "~{OE}_25") (pintype "input"))
      (node (ref "IC2") (pin "28") (pinfunction "GND_28") (pintype "power_in"))
      (node (ref "IC2") (pin "34") (pinfunction "GND_34") (pintype "power_in"))
      (node (ref "IC2") (pin "39") (pinfunction "GND_39") (pintype "power_in"))
      (node (ref "IC2") (pin "4") (pinfunction "GND_4") (pintype "power_in"))
      (node (ref "IC2") (pin "45") (pinfunction "GND_45") (pintype "power_in"))
      (node (ref "IC2") (pin "48") (pinfunction "~{OE}_48") (pintype "input"))
      (node (ref "IC3") (pin "1") (pinfunction "~{OE}_1") (pintype "input"))
      (node (ref "IC3") (pin "10") (pinfunction "GND_10") (pintype "power_in"))
      (node (ref "IC3") (pin "15") (pinfunction "GND_15") (pintype "power_in"))
      (node (ref "IC3") (pin "21") (pinfunction "GND_21") (pintype "power_in"))
      (node (ref "IC3") (pin "24") (pinfunction "~{OE}_24") (pintype "input"))
      (node (ref "IC3") (pin "25") (pinfunction "~{OE}_25") (pintype "input"))
      (node (ref "IC3") (pin "28") (pinfunction "GND_28") (pintype "power_in"))
      (node (ref "IC3") (pin "34") (pinfunction "GND_34") (pintype "power_in"))
      (node (ref "IC3") (pin "39") (pinfunction "GND_39") (pintype "power_in"))
      (node (ref "IC3") (pin "4") (pinfunction "GND_4") (pintype "power_in"))
      (node (ref "IC3") (pin "45") (pinfunction "GND_45") (pintype "power_in"))
      (node (ref "IC3") (pin "48") (pinfunction "~{OE}_48") (pintype "input"))
      (node (ref "IC4") (pin "13") (pinfunction "GND_13") (pintype "bidirectional"))
      (node (ref "IC4") (pin "37") (pinfunction "GND_37") (pintype "bidirectional"))
      (node (ref "IC4") (pin "7") (pinfunction "~{CE}_7") (pintype "input"))
      (node (ref "IC5") (pin "104") (pinfunction "GND_104") (pintype "power_in"))
      (node (ref "IC5") (pin "116") (pinfunction "GND_116") (pintype "power_in"))
      (node (ref "IC5") (pin "125") (pinfunction "GND_125") (pintype "power_in"))
      (node (ref "IC5") (pin "133") (pinfunction "GND_133") (pintype "power_in"))
      (node (ref "IC5") (pin "137") (pinfunction "GND_137") (pintype "power_in"))
      (node (ref "IC5") (pin "142") (pinfunction "GND_142") (pintype "power_in"))
      (node (ref "IC5") (pin "3") (pinfunction "GND_3") (pintype "power_in"))
      (node (ref "IC5") (pin "4") (pinfunction "GND_4") (pintype "power_in"))
      (node (ref "IC5") (pin "42") (pinfunction "GND_42") (pintype "power_in"))
      (node (ref "IC5") (pin "53") (pinfunction "GND_53") (pintype "power_in"))
      (node (ref "IC5") (pin "63") (pinfunction "GND_63") (pintype "power_in"))
      (node (ref "IC5") (pin "68") (pinfunction "GND_68") (pintype "power_in"))
      (node (ref "IC5") (pin "83") (pinfunction "GND_83") (pintype "power_in"))
      (node (ref "IC5") (pin "95") (pinfunction "GND_95") (pintype "power_in"))
      (node (ref "IC5") (pin "GB@4") (pinfunction "GP_GB@4") (pintype "power_in"))
      (node (ref "IC5") (pin "GP@1") (pinfunction "GP_GP@1") (pintype "power_in"))
      (node (ref "IC5") (pin "GP@2") (pinfunction "GP_GP@2") (pintype "power_in"))
      (node (ref "IC5") (pin "GP@3") (pinfunction "GP_GP@3") (pintype "power_in"))
      (node (ref "IC5") (pin "GP@5") (pinfunction "GP_GP@5") (pintype "power_in"))
      (node (ref "IC6") (pin "5") (pinfunction "GND_5") (pintype "power_in"))
      (node (ref "IC7") (pin "1") (pinfunction "GND_1") (pintype "power_in"))
      (node (ref "IC8") (pin "3") (pinfunction "GND_3") (pintype "power_in"))
      (node (ref "IC8") (pin "6") (pinfunction "S0_6") (pintype "input"))
      (node (ref "IC9") (pin "2") (pinfunction "GND_2") (pintype "power_in"))
      (node (ref "LED1") (pin "K") (pinfunction "C_K") (pintype "passive"))
      (node (ref "LED2") (pin "K") (pinfunction "C_K") (pintype "passive"))
      (node (ref "LED34") (pin "K") (pinfunction "C_K") (pintype "passive"))
      (node (ref "R1") (pin "1") (pinfunction "1_1") (pintype "passive"))
      (node (ref "R10") (pin "1") (pinfunction "1_1") (pintype "passive"))
      (node (ref "R25") (pin "1") (pinfunction "1_1") (pintype "passive"))
      (node (ref "R26") (pin "1") (pinfunction "1_1") (pintype "passive"))
      (node (ref "R6") (pin "2") (pinfunction "2_2") (pintype "passive"))
    )
    (net (code "107") (name "HD") (class "Default")
      (node (ref "CN7") (pin "4") (pinfunction "S_4") (pintype "passive"))
      (node (ref "R19") (pin "1") (pinfunction "1_1") (pintype "passive"))
    )
    (net (code "108") (name "INT2") (class "Default")
      (node (ref "CN1") (pin "63") (pinfunction "~{INT2}_63") (pintype "bidirectional"))
      (node (ref "IC1") (pin "11") (pinfunction "B3_11") (pintype "bidirectional"))
    )
    (net (code "109") (name "IORD") (class "Default")
      (node (ref "CN1") (pin "71") (pinfunction "~{IORD}_71") (pintype "bidirectional"))
      (node (ref "IC1") (pin "8") (pinfunction "B1_8") (pintype "bidirectional"))
    )
    (net (code "110") (name "IOWR") (class "Default")
      (node (ref "CN1") (pin "72") (pinfunction "~{IOWR}_72") (pintype "bidirectional"))
      (node (ref "IC1") (pin "6") (pinfunction "B4_6") (pintype "bidirectional"))
    )
    (net (code "111") (name "LB") (class "Default")
      (node (ref "IC4") (pin "42") (pinfunction "~{LB}_42") (pintype "input"))
      (node (ref "IC5") (pin "79") (pinfunction "GPIO79_79") (pintype "bidirectional"))
    )
    (net (code "112") (name "LED") (class "Default")
      (node (ref "IC5") (pin "120") (pinfunction "GPIO120_120") (pintype "bidirectional"))
      (node (ref "R23") (pin "1") (pinfunction "1_1") (pintype "passive"))
    )
    (net (code "113") (name "MISO") (class "Default")
      (node (ref "CN2") (pin "21") (pinfunction "MISO_21") (pintype "bidirectional"))
      (node (ref "IC5") (pin "56") (pinfunction "GPIO56_56") (pintype "bidirectional"))
    )
    (net (code "114") (name "MOSI") (class "Default")
      (node (ref "CN2") (pin "19") (pinfunction "MOSI_19") (pintype "bidirectional"))
      (node (ref "IC5") (pin "55") (pinfunction "GPIO55_55") (pintype "bidirectional"))
    )
    (net (code "115") (name "Net-(CN2-ID_SC)") (class "Default")
      (node (ref "CN2") (pin "28") (pinfunction "ID_SC_28") (pintype "bidirectional"))
      (node (ref "IC10") (pin "6") (pinfunction "SCL_6") (pintype "input"))
      (node (ref "R17") (pin "2") (pinfunction "2_2") (pintype "passive"))
    )
    (net (code "116") (name "Net-(CN2-ID_SD)") (class "Default")
      (node (ref "CN2") (pin "27") (pinfunction "ID_SD_27") (pintype "bidirectional"))
      (node (ref "IC10") (pin "5") (pinfunction "SDA_5") (pintype "bidirectional"))
      (node (ref "R18") (pin "1") (pinfunction "1_1") (pintype "passive"))
    )
    (net (code "117") (name "Net-(CN2-SCL)") (class "Default")
      (node (ref "CN2") (pin "5") (pinfunction "SCL_5") (pintype "bidirectional"))
      (node (ref "CN6") (pin "3") (pinfunction "3_3") (pintype "passive"))
      (node (ref "R21") (pin "2") (pinfunction "2_2") (pintype "passive"))
    )
    (net (code "118") (name "Net-(CN2-SDA)") (class "Default")
      (node (ref "CN2") (pin "3") (pinfunction "SDA_3") (pintype "bidirectional"))
      (node (ref "CN6") (pin "4") (pinfunction "4_4") (pintype "passive"))
      (node (ref "R20") (pin "2") (pinfunction "2_2") (pintype "passive"))
    )
    (net (code "119") (name "Net-(CN4-Pad4)") (class "Default")
      (node (ref "CN4") (pin "4") (pinfunction "4_4") (pintype "passive"))
      (node (ref "T4") (pin "C") (pinfunction "C_C") (pintype "passive"))
    )
    (net (code "120") (name "Net-(D1-A1)") (class "Default")
      (node (ref "D1") (pin "1") (pinfunction "A1_1") (pintype "passive"))
      (node (ref "R28") (pin "1") (pinfunction "1_1") (pintype "passive"))
    )
    (net (code "121") (name "Net-(D1-A2)") (class "Default")
      (node (ref "D1") (pin "2") (pinfunction "A2_2") (pintype "passive"))
      (node (ref "R23") (pin "2") (pinfunction "2_2") (pintype "passive"))
      (node (ref "T2") (pin "B") (pinfunction "B_B") (pintype "passive"))
    )
    (net (code "122") (name "Net-(D1-C)") (class "Default")
      (node (ref "D1") (pin "3") (pinfunction "C_3") (pintype "passive"))
      (node (ref "T3") (pin "B") (pinfunction "B_B") (pintype "passive"))
    )
    (net (code "123") (name "Net-(IC1D-B4)") (class "Default")
      (node (ref "IC1") (pin "23") (pinfunction "B4_23") (pintype "bidirectional"))
      (node (ref "R5") (pin "2") (pinfunction "2_2") (pintype "passive"))
    )
    (net (code "124") (name "Net-(IC2A-B1)") (class "Default")
      (node (ref "IC2") (pin "2") (pinfunction "B1_2") (pintype "bidirectional"))
      (node (ref "R11") (pin "8") (pinfunction "P$2_8") (pintype "passive"))
    )
    (net (code "125") (name "Net-(IC2A-B2)") (class "Default")
      (node (ref "IC2") (pin "3") (pinfunction "B2_3") (pintype "bidirectional"))
      (node (ref "R11") (pin "7") (pinfunction "P$2_7") (pintype "passive"))
    )
    (net (code "126") (name "Net-(IC2A-B3)") (class "Default")
      (node (ref "IC2") (pin "5") (pinfunction "B3_5") (pintype "bidirectional"))
      (node (ref "R11") (pin "6") (pinfunction "P$2_6") (pintype "passive"))
    )
    (net (code "127") (name "Net-(IC2A-B4)") (class "Default")
      (node (ref "IC2") (pin "6") (pinfunction "B4_6") (pintype "bidirectional"))
      (node (ref "R11") (pin "5") (pinfunction "P$2_5") (pintype "passive"))
    )
    (net (code "128") (name "Net-(IC2B-B1)") (class "Default")
      (node (ref "IC2") (pin "8") (pinfunction "B1_8") (pintype "bidirectional"))
      (node (ref "R12") (pin "8") (pinfunction "P$2_8") (pintype "passive"))
    )
    (net (code "129") (name "Net-(IC2B-B2)") (class "Default")
      (node (ref "IC2") (pin "9") (pinfunction "B2_9") (pintype "bidirectional"))
      (node (ref "R12") (pin "7") (pinfunction "P$2_7") (pintype "passive"))
    )
    (net (code "130") (name "Net-(IC2B-B3)") (class "Default")
      (node (ref "IC2") (pin "11") (pinfunction "B3_11") (pintype "bidirectional"))
      (node (ref "R12") (pin "6") (pinfunction "P$2_6") (pintype "passive"))
    )
    (net (code "131") (name "Net-(IC2B-B4)") (class "Default")
      (node (ref "IC2") (pin "12") (pinfunction "B4_12") (pintype "bidirectional"))
      (node (ref "R12") (pin "5") (pinfunction "P$2_5") (pintype "passive"))
    )
    (net (code "132") (name "Net-(IC2C-B1)") (class "Default")
      (node (ref "IC2") (pin "13") (pinfunction "B1_13") (pintype "bidirectional"))
      (node (ref "R13") (pin "8") (pinfunction "P$2_8") (pintype "passive"))
    )
    (net (code "133") (name "Net-(IC2C-B2)") (class "Default")
      (node (ref "IC2") (pin "14") (pinfunction "B2_14") (pintype "bidirectional"))
      (node (ref "R13") (pin "7") (pinfunction "P$2_7") (pintype "passive"))
    )
    (net (code "134") (name "Net-(IC2C-B3)") (class "Default")
      (node (ref "IC2") (pin "16") (pinfunction "B3_16") (pintype "bidirectional"))
      (node (ref "R13") (pin "6") (pinfunction "P$2_6") (pintype "passive"))
    )
    (net (code "135") (name "Net-(IC2C-B4)") (class "Default")
      (node (ref "IC2") (pin "17") (pinfunction "B4_17") (pintype "bidirectional"))
      (node (ref "R13") (pin "5") (pinfunction "P$2_5") (pintype "passive"))
    )
    (net (code "136") (name "Net-(IC2D-B1)") (class "Default")
      (node (ref "IC2") (pin "19") (pinfunction "B1_19") (pintype "bidirectional"))
      (node (ref "R14") (pin "8") (pinfunction "P$2_8") (pintype "passive"))
    )
    (net (code "137") (name "Net-(IC2D-B2)") (class "Default")
      (node (ref "IC2") (pin "20") (pinfunction "B2_20") (pintype "bidirectional"))
      (node (ref "R14") (pin "7") (pinfunction "P$2_7") (pintype "passive"))
    )
    (net (code "138") (name "Net-(IC2D-B3)") (class "Default")
      (node (ref "IC2") (pin "22") (pinfunction "B3_22") (pintype "bidirectional"))
      (node (ref "R14") (pin "6") (pinfunction "P$2_6") (pintype "passive"))
    )
    (net (code "139") (name "Net-(IC2D-B4)") (class "Default")
      (node (ref "IC2") (pin "23") (pinfunction "B4_23") (pintype "bidirectional"))
      (node (ref "R14") (pin "5") (pinfunction "P$2_5") (pintype "passive"))
    )
    (net (code "140") (name "Net-(IC5C-GPIO27{slash}CLK0P)") (class "Default")
      (node (ref "IC5") (pin "27") (pinfunction "GPIO27/CLK0P_27") (pintype "bidirectional"))
      (node (ref "IC8") (pin "5") (pinfunction "CLKOUT_5") (pintype "output"))
    )
    (net (code "141") (name "Net-(IC5G-GPIO97{slash}VREFB6N0)") (class "Default")
      (node (ref "IC5") (pin "97") (pinfunction "GPIO97/VREFB6N0_97") (pintype "bidirectional"))
      (node (ref "IC6") (pin "8") (pinfunction "SCL_8") (pintype "input"))
      (node (ref "R4") (pin "1") (pinfunction "1_1") (pintype "passive"))
    )
    (net (code "142") (name "Net-(IC5H-GPIO112{slash}VREFB7N0)") (class "Default")
      (node (ref "IC5") (pin "112") (pinfunction "GPIO112/VREFB7N0_112") (pintype "bidirectional"))
      (node (ref "IC6") (pin "7") (pinfunction "SDA_7") (pintype "bidirectional"))
      (node (ref "R3") (pin "1") (pinfunction "1_1") (pintype "passive"))
    )
    (net (code "143") (name "Net-(IC5I-GPIO126{slash}CONFIG_SEL)") (class "Default")
      (node (ref "IC5") (pin "126") (pinfunction "GPIO126/CONFIG_SEL_126") (pintype "bidirectional"))
      (node (ref "R6") (pin "1") (pinfunction "1_1") (pintype "passive"))
    )
    (net (code "144") (name "Net-(IC6-VBAT)") (class "Default")
      (node (ref "BAT1") (pin "+@1") (pinfunction "+_+@1") (pintype "power_in"))
      (node (ref "BAT1") (pin "+@2") (pinfunction "+_+@2") (pintype "power_in"))
      (node (ref "BAT1") (pin "+@3") (pinfunction "+_+@3") (pintype "power_in"))
      (node (ref "BAT1") (pin "+@4") (pinfunction "+_+@4") (pintype "power_in"))
      (node (ref "IC6") (pin "6") (pinfunction "VBAT_6") (pintype "power_in"))
    )
    (net (code "145") (name "Net-(IC7-SW)") (class "Default")
      (node (ref "C4") (pin "2") (pinfunction "2_2") (pintype "passive"))
      (node (ref "IC7") (pin "2") (pinfunction "SW_2") (pintype "power_in"))
      (node (ref "L2") (pin "1") (pinfunction "1_1") (pintype "passive"))
    )
    (net (code "146") (name "Net-(IC7-VBST)") (class "Default")
      (node (ref "C4") (pin "1") (pinfunction "1_1") (pintype "passive"))
      (node (ref "IC7") (pin "6") (pinfunction "VBST_6") (pintype "passive"))
    )
    (net (code "147") (name "Net-(IC7-VFB)") (class "Default")
      (node (ref "IC7") (pin "4") (pinfunction "VFB_4") (pintype "passive"))
      (node (ref "R1") (pin "2") (pinfunction "2_2") (pintype "passive"))
      (node (ref "R2") (pin "1") (pinfunction "1_1") (pintype "passive"))
    )
    (net (code "148") (name "Net-(IC10-WP)") (class "Default")
      (node (ref "IC10") (pin "7") (pinfunction "WP_7") (pintype "input"))
      (node (ref "R16") (pin "1") (pinfunction "1_1") (pintype "passive"))
    )
    (net (code "149") (name "Net-(LED1-PadA)") (class "Default")
      (node (ref "LED1") (pin "A") (pinfunction "A_A") (pintype "passive"))
      (node (ref "R7") (pin "2") (pinfunction "2_2") (pintype "passive"))
    )
    (net (code "150") (name "Net-(LED2-PadA)") (class "Default")
      (node (ref "LED2") (pin "A") (pinfunction "A_A") (pintype "passive"))
      (node (ref "R15") (pin "2") (pinfunction "2_2") (pintype "passive"))
    )
    (net (code "151") (name "Net-(LED34-PadAG)") (class "Default")
      (node (ref "LED34") (pin "AG") (pinfunction "AG_AG") (pintype "passive"))
      (node (ref "R19") (pin "2") (pinfunction "2_2") (pintype "passive"))
    )
    (net (code "152") (name "Net-(LED34-PadAR)") (class "Default")
      (node (ref "LED34") (pin "AR") (pinfunction "AR_AR") (pintype "passive"))
      (node (ref "R22") (pin "2") (pinfunction "2_2") (pintype "passive"))
    )
    (net (code "153") (name "Net-(R24-Pad1)") (class "Default")
      (node (ref "R24") (pin "1") (pinfunction "1_1") (pintype "passive"))
      (node (ref "T1") (pin "B") (pinfunction "B_B") (pintype "passive"))
      (node (ref "T2") (pin "C") (pinfunction "C_C") (pintype "passive"))
    )
    (net (code "154") (name "Net-(R25-Pad2)") (class "Default")
      (node (ref "R25") (pin "2") (pinfunction "2_2") (pintype "passive"))
      (node (ref "T2") (pin "E") (pinfunction "E_E") (pintype "passive"))
    )
    (net (code "155") (name "Net-(R26-Pad2)") (class "Default")
      (node (ref "R26") (pin "2") (pinfunction "2_2") (pintype "passive"))
      (node (ref "T3") (pin "E") (pinfunction "E_E") (pintype "passive"))
    )
    (net (code "156") (name "Net-(R27-Pad1)") (class "Default")
      (node (ref "R27") (pin "1") (pinfunction "1_1") (pintype "passive"))
      (node (ref "T3") (pin "C") (pinfunction "C_C") (pintype "passive"))
      (node (ref "T4") (pin "B") (pinfunction "B_B") (pintype "passive"))
    )
    (net (code "157") (name "OE") (class "Default")
      (node (ref "IC4") (pin "44") (pinfunction "~{OE}_44") (pintype "input"))
      (node (ref "IC5") (pin "84") (pinfunction "GPIO84_84") (pintype "bidirectional"))
    )
    (net (code "158") (name "PW") (class "Default")
      (node (ref "CN7") (pin "2") (pinfunction "S_2") (pintype "passive"))
      (node (ref "R7") (pin "1") (pinfunction "1_1") (pintype "passive"))
    )
    (net (code "159") (name "RPI_IRQ") (class "Default")
      (node (ref "CN2") (pin "22") (pinfunction "GPIO25_22") (pintype "bidirectional"))
      (node (ref "IC5") (pin "61") (pinfunction "GPIO61/VREFB4N0_61") (pintype "bidirectional"))
    )
    (net (code "160") (name "RTC_CS") (class "Default")
      (node (ref "CN1") (pin "73") (pinfunction "~{RTC_CS}_73") (pintype "bidirectional"))
      (node (ref "IC1") (pin "9") (pinfunction "B2_9") (pintype "bidirectional"))
    )
    (net (code "161") (name "SCE") (class "Default")
      (node (ref "CN2") (pin "24") (pinfunction "CE0_24") (pintype "bidirectional"))
      (node (ref "IC5") (pin "80") (pinfunction "GPIO80/VREFB5N0_80") (pintype "bidirectional"))
    )
    (net (code "162") (name "SCLK") (class "Default")
      (node (ref "CN2") (pin "23") (pinfunction "SCLK_23") (pintype "bidirectional"))
      (node (ref "IC5") (pin "57") (pinfunction "GPIO57_57") (pintype "bidirectional"))
    )
    (net (code "163") (name "SRA0") (class "Default")
      (node (ref "IC4") (pin "5") (pinfunction "A0_5") (pintype "input"))
      (node (ref "IC5") (pin "93") (pinfunction "GPIO93_93") (pintype "bidirectional"))
    )
    (net (code "164") (name "SRA1") (class "Default")
      (node (ref "IC4") (pin "4") (pinfunction "A1_4") (pintype "input"))
      (node (ref "IC5") (pin "92") (pinfunction "GPIO92_92") (pintype "bidirectional"))
    )
    (net (code "165") (name "SRA2") (class "Default")
      (node (ref "IC4") (pin "3") (pinfunction "A2_3") (pintype "input"))
      (node (ref "IC5") (pin "91") (pinfunction "GPIO91/CLK3N_91") (pintype "bidirectional"))
    )
    (net (code "166") (name "SRA3") (class "Default")
      (node (ref "IC4") (pin "2") (pinfunction "A3_2") (pintype "input"))
      (node (ref "IC5") (pin "90") (pinfunction "GPIO90/CLK3P_90") (pintype "bidirectional"))
    )
    (net (code "167") (name "SRA4") (class "Default")
      (node (ref "IC4") (pin "1") (pinfunction "A4_1") (pintype "input"))
      (node (ref "IC5") (pin "89") (pinfunction "GPIO89/CLK2N_89") (pintype "bidirectional"))
    )
    (net (code "168") (name "SRA5") (class "Default")
      (node (ref "IC4") (pin "48") (pinfunction "A5_48") (pintype "input"))
      (node (ref "IC5") (pin "88") (pinfunction "GPIO88/CLK2P_88") (pintype "bidirectional"))
    )
    (net (code "169") (name "SRA6") (class "Default")
      (node (ref "IC4") (pin "47") (pinfunction "A6_47") (pintype "input"))
      (node (ref "IC5") (pin "87") (pinfunction "GPIO87_87") (pintype "bidirectional"))
    )
    (net (code "170") (name "SRA7") (class "Default")
      (node (ref "IC4") (pin "46") (pinfunction "A7_46") (pintype "input"))
      (node (ref "IC5") (pin "86") (pinfunction "GPIO86_86") (pintype "bidirectional"))
    )
    (net (code "171") (name "SRA8") (class "Default")
      (node (ref "IC4") (pin "45") (pinfunction "A8_45") (pintype "input"))
      (node (ref "IC5") (pin "85") (pinfunction "GPIO85_85") (pintype "bidirectional"))
    )
    (net (code "172") (name "SRA9") (class "Default")
      (node (ref "IC4") (pin "30") (pinfunction "A9_30") (pintype "input"))
      (node (ref "IC5") (pin "62") (pinfunction "GPIO62_62") (pintype "bidirectional"))
    )
    (net (code "173") (name "SRA10") (class "Default")
      (node (ref "IC4") (pin "29") (pinfunction "A10_29") (pintype "input"))
      (node (ref "IC5") (pin "64") (pinfunction "GPIO64_64") (pintype "bidirectional"))
    )
    (net (code "174") (name "SRA11") (class "Default")
      (node (ref "IC4") (pin "28") (pinfunction "A11_28") (pintype "input"))
      (node (ref "IC5") (pin "65") (pinfunction "GPIO65_65") (pintype "bidirectional"))
    )
    (net (code "175") (name "SRA12") (class "Default")
      (node (ref "IC4") (pin "27") (pinfunction "A12_27") (pintype "input"))
      (node (ref "IC5") (pin "66") (pinfunction "GPIO66_66") (pintype "bidirectional"))
    )
    (net (code "176") (name "SRA13") (class "Default")
      (node (ref "IC4") (pin "26") (pinfunction "A13_26") (pintype "input"))
      (node (ref "IC5") (pin "69") (pinfunction "GPIO69_69") (pintype "bidirectional"))
    )
    (net (code "177") (name "SRA14") (class "Default")
      (node (ref "IC4") (pin "25") (pinfunction "A14_25") (pintype "input"))
      (node (ref "IC5") (pin "70") (pinfunction "GPIO70_70") (pintype "bidirectional"))
    )
    (net (code "178") (name "SRA15") (class "Default")
      (node (ref "IC4") (pin "24") (pinfunction "A15_24") (pintype "input"))
      (node (ref "IC5") (pin "110") (pinfunction "GPIO110_110") (pintype "bidirectional"))
    )
    (net (code "179") (name "SRA16") (class "Default")
      (node (ref "IC4") (pin "23") (pinfunction "A16_23") (pintype "input"))
      (node (ref "IC5") (pin "111") (pinfunction "GPIO111_111") (pintype "bidirectional"))
    )
    (net (code "180") (name "SRA17") (class "Default")
      (node (ref "IC4") (pin "22") (pinfunction "A17_22") (pintype "input"))
      (node (ref "IC5") (pin "113") (pinfunction "GPIO113_113") (pintype "bidirectional"))
    )
    (net (code "181") (name "SRA18") (class "Default")
      (node (ref "IC4") (pin "21") (pinfunction "A18_21") (pintype "input"))
      (node (ref "IC5") (pin "114") (pinfunction "GPIO114_114") (pintype "bidirectional"))
    )
    (net (code "182") (name "SRA19") (class "Default")
      (node (ref "IC4") (pin "20") (pinfunction "A19_20") (pintype "input"))
      (node (ref "IC5") (pin "118") (pinfunction "GPIO118_118") (pintype "bidirectional"))
    )
    (net (code "183") (name "SRD0") (class "Default")
      (node (ref "IC4") (pin "8") (pinfunction "D0_8") (pintype "bidirectional"))
      (node (ref "IC5") (pin "96") (pinfunction "GPIO96/DPCLK3_96") (pintype "bidirectional"))
    )
    (net (code "184") (name "SRD1") (class "Default")
      (node (ref "IC4") (pin "9") (pinfunction "D1_9") (pintype "bidirectional"))
      (node (ref "IC5") (pin "98") (pinfunction "GPIO98/DPCLK2_98") (pintype "bidirectional"))
    )
    (net (code "185") (name "SRD2") (class "Default")
      (node (ref "IC4") (pin "10") (pinfunction "D2_10") (pintype "bidirectional"))
      (node (ref "IC5") (pin "99") (pinfunction "GPIO99_99") (pintype "bidirectional"))
    )
    (net (code "186") (name "SRD3") (class "Default")
      (node (ref "IC4") (pin "11") (pinfunction "D3_11") (pintype "bidirectional"))
      (node (ref "IC5") (pin "100") (pinfunction "GPIO100_100") (pintype "bidirectional"))
    )
    (net (code "187") (name "SRD4") (class "Default")
      (node (ref "IC4") (pin "14") (pinfunction "D4_14") (pintype "bidirectional"))
      (node (ref "IC5") (pin "101") (pinfunction "GPIO101_101") (pintype "bidirectional"))
    )
    (net (code "188") (name "SRD5") (class "Default")
      (node (ref "IC4") (pin "15") (pinfunction "D5_15") (pintype "bidirectional"))
      (node (ref "IC5") (pin "102") (pinfunction "GPIO102_102") (pintype "bidirectional"))
    )
    (net (code "189") (name "SRD6") (class "Default")
      (node (ref "IC4") (pin "16") (pinfunction "D6_16") (pintype "bidirectional"))
      (node (ref "IC5") (pin "105") (pinfunction "GPIO105_105") (pintype "bidirectional"))
    )
    (net (code "190") (name "SRD7") (class "Default")
      (node (ref "IC4") (pin "17") (pinfunction "D7_17") (pintype "bidirectional"))
      (node (ref "IC5") (pin "106") (pinfunction "GPIO106_106") (pintype "bidirectional"))
    )
    (net (code "191") (name "SRD8") (class "Default")
      (node (ref "IC4") (pin "32") (pinfunction "D8_32") (pintype "bidirectional"))
      (node (ref "IC5") (pin "60") (pinfunction "GPIO60_60") (pintype "bidirectional"))
    )
    (net (code "192") (name "SRD9") (class "Default")
      (node (ref "IC4") (pin "33") (pinfunction "D9_33") (pintype "bidirectional"))
      (node (ref "IC5") (pin "59") (pinfunction "GPIO59_59") (pintype "bidirectional"))
    )
    (net (code "193") (name "SRD10") (class "Default")
      (node (ref "IC4") (pin "34") (pinfunction "D10_34") (pintype "bidirectional"))
      (node (ref "IC5") (pin "58") (pinfunction "GPIO58_58") (pintype "bidirectional"))
    )
    (net (code "194") (name "SRD11") (class "Default")
      (node (ref "IC4") (pin "35") (pinfunction "D11_35") (pintype "bidirectional"))
      (node (ref "IC5") (pin "74") (pinfunction "GPIO74_74") (pintype "bidirectional"))
    )
    (net (code "195") (name "SRD12") (class "Default")
      (node (ref "IC4") (pin "38") (pinfunction "D12_38") (pintype "bidirectional"))
      (node (ref "IC5") (pin "75") (pinfunction "GPIO75_75") (pintype "bidirectional"))
    )
    (net (code "196") (name "SRD13") (class "Default")
      (node (ref "IC4") (pin "39") (pinfunction "D13_39") (pintype "bidirectional"))
      (node (ref "IC5") (pin "76") (pinfunction "GPIO76_76") (pintype "bidirectional"))
    )
    (net (code "197") (name "SRD14") (class "Default")
      (node (ref "IC4") (pin "40") (pinfunction "D14_40") (pintype "bidirectional"))
      (node (ref "IC5") (pin "77") (pinfunction "GPIO77_77") (pintype "bidirectional"))
    )
    (net (code "198") (name "SRD15") (class "Default")
      (node (ref "IC4") (pin "41") (pinfunction "D15_41") (pintype "bidirectional"))
      (node (ref "IC5") (pin "78") (pinfunction "GPIO78_78") (pintype "bidirectional"))
    )
    (net (code "199") (name "TCK") (class "Default")
      (node (ref "CN2") (pin "11") (pinfunction "GPIO17_11") (pintype "bidirectional"))
      (node (ref "IC5") (pin "18") (pinfunction "GPIO18/TCK_18") (pintype "bidirectional"))
      (node (ref "R10") (pin "2") (pinfunction "2_2") (pintype "passive"))
    )
    (net (code "200") (name "TDI") (class "Default")
      (node (ref "CN2") (pin "16") (pinfunction "GPIO23_16") (pintype "bidirectional"))
      (node (ref "IC5") (pin "19") (pinfunction "GPIO19/TDI_19") (pintype "bidirectional"))
      (node (ref "R9") (pin "1") (pinfunction "1_1") (pintype "passive"))
    )
    (net (code "201") (name "TDO") (class "Default")
      (node (ref "CN2") (pin "13") (pinfunction "GPIO27_13") (pintype "bidirectional"))
      (node (ref "IC5") (pin "20") (pinfunction "GPIO20/TDO_20") (pintype "bidirectional"))
    )
    (net (code "202") (name "TMS") (class "Default")
      (node (ref "CN2") (pin "15") (pinfunction "GPIO22_15") (pintype "bidirectional"))
      (node (ref "IC5") (pin "16") (pinfunction "GPIO16/TMS_16") (pintype "bidirectional"))
      (node (ref "R8") (pin "1") (pinfunction "1_1") (pintype "passive"))
    )
    (net (code "203") (name "UB") (class "Default")
      (node (ref "IC4") (pin "43") (pinfunction "~{UB}_43") (pintype "input"))
      (node (ref "IC5") (pin "81") (pinfunction "GPIO81_81") (pintype "bidirectional"))
    )
    (net (code "204") (name "VCC{slash}2") (class "Default")
      (node (ref "C8") (pin "1") (pinfunction "1_1") (pintype "passive"))
      (node (ref "CN2") (pin "1") (pinfunction "3V3_1") (pintype "power_in"))
      (node (ref "CN2") (pin "17") (pinfunction "3V3_17") (pintype "power_in"))
      (node (ref "CN6") (pin "2") (pinfunction "2_2") (pintype "passive"))
      (node (ref "IC10") (pin "8") (pinfunction "VCC_8") (pintype "power_in"))
      (node (ref "R16") (pin "2") (pinfunction "2_2") (pintype "passive"))
      (node (ref "R17") (pin "1") (pinfunction "1_1") (pintype "passive"))
      (node (ref "R18") (pin "2") (pinfunction "2_2") (pintype "passive"))
      (node (ref "R20") (pin "1") (pinfunction "1_1") (pintype "passive"))
      (node (ref "R21") (pin "1") (pinfunction "1_1") (pintype "passive"))
    )
    (net (code "205") (name "WE") (class "Default")
      (node (ref "IC4") (pin "18") (pinfunction "~{WE}_18") (pintype "input"))
      (node (ref "IC5") (pin "119") (pinfunction "GPIO119_119") (pintype "bidirectional"))
    )
    (net (code "206") (name "unconnected-(CN1-+12V-Pad79)") (class "Default")
      (node (ref "CN1") (pin "79") (pinfunction "+12V_79") (pintype "bidirectional"))
    )
    (net (code "207") (name "unconnected-(CN1--12V-Pad80)") (class "Default")
      (node (ref "CN1") (pin "80") (pinfunction "-12V_80") (pintype "bidirectional"))
    )
    (net (code "208") (name "unconnected-(CN1-14MHZ_A-Pad67)") (class "Default")
      (node (ref "CN1") (pin "67") (pinfunction "14MHZ_A_67") (pintype "bidirectional"))
    )
    (net (code "209") (name "unconnected-(CN1-D4-Pad53)") (class "Default")
      (node (ref "CN1") (pin "53") (pinfunction "D4_53") (pintype "bidirectional"))
    )
    (net (code "210") (name "unconnected-(CN1-D5-Pad54)") (class "Default")
      (node (ref "CN1") (pin "54") (pinfunction "D5_54") (pintype "bidirectional"))
    )
    (net (code "211") (name "unconnected-(CN1-D6-Pad55)") (class "Default")
      (node (ref "CN1") (pin "55") (pinfunction "D6_55") (pintype "bidirectional"))
    )
    (net (code "212") (name "unconnected-(CN1-D7-Pad56)") (class "Default")
      (node (ref "CN1") (pin "56") (pinfunction "D7_56") (pintype "bidirectional"))
    )
    (net (code "213") (name "unconnected-(CN1-LEFT-Pad65)") (class "Default")
      (node (ref "CN1") (pin "65") (pinfunction "LEFT_65") (pintype "bidirectional"))
    )
    (net (code "214") (name "unconnected-(CN1-RGA1-Pad48)") (class "Default")
      (node (ref "CN1") (pin "48") (pinfunction "RGA1_48") (pintype "bidirectional"))
    )
    (net (code "215") (name "unconnected-(CN1-RGA2-Pad47)") (class "Default")
      (node (ref "CN1") (pin "47") (pinfunction "RGA2_47") (pintype "bidirectional"))
    )
    (net (code "216") (name "unconnected-(CN1-RGA3-Pad46)") (class "Default")
      (node (ref "CN1") (pin "46") (pinfunction "RGA3_46") (pintype "bidirectional"))
    )
    (net (code "217") (name "unconnected-(CN1-RGA4-Pad45)") (class "Default")
      (node (ref "CN1") (pin "45") (pinfunction "RGA4_45") (pintype "bidirectional"))
    )
    (net (code "218") (name "unconnected-(CN1-RGA5-Pad44)") (class "Default")
      (node (ref "CN1") (pin "44") (pinfunction "RGA5_44") (pintype "bidirectional"))
    )
    (net (code "219") (name "unconnected-(CN1-RGA6-Pad43)") (class "Default")
      (node (ref "CN1") (pin "43") (pinfunction "RGA6_43") (pintype "bidirectional"))
    )
    (net (code "220") (name "unconnected-(CN1-RGA7-Pad42)") (class "Default")
      (node (ref "CN1") (pin "42") (pinfunction "RGA7_42") (pintype "bidirectional"))
    )
    (net (code "221") (name "unconnected-(CN1-RGA8-Pad41)") (class "Default")
      (node (ref "CN1") (pin "41") (pinfunction "RGA8_41") (pintype "bidirectional"))
    )
    (net (code "222") (name "unconnected-(CN1-RIGHT-Pad66)") (class "Default")
      (node (ref "CN1") (pin "66") (pinfunction "RIGHT_66") (pintype "bidirectional"))
    )
    (net (code "223") (name "unconnected-(CN1-~{INT6}-Pad64)") (class "Default")
      (node (ref "CN1") (pin "64") (pinfunction "~{INT6}_64") (pintype "bidirectional"))
    )
    (net (code "224") (name "unconnected-(CN1-~{NET_CS}-Pad61)") (class "Default")
      (node (ref "CN1") (pin "61") (pinfunction "~{NET_CS}_61") (pintype "bidirectional"))
    )
    (net (code "225") (name "unconnected-(CN1-~{RESET}-Pad70)") (class "Default")
      (node (ref "CN1") (pin "70") (pinfunction "~{RESET}_70") (pintype "bidirectional"))
    )
    (net (code "226") (name "unconnected-(CN1-~{SENSE}-Pad74)") (class "Default")
      (node (ref "CN1") (pin "74") (pinfunction "~{SENSE}_74") (pintype "bidirectional"))
    )
    (net (code "227") (name "unconnected-(CN1-~{SPARE_CS}-Pad62)") (class "Default")
      (node (ref "CN1") (pin "62") (pinfunction "~{SPARE_CS}_62") (pintype "bidirectional"))
    )
    (net (code "228") (name "unconnected-(CN1-~{TEST}-Pad68)") (class "Default")
      (node (ref "CN1") (pin "68") (pinfunction "~{TEST}_68") (pintype "bidirectional"))
    )
    (net (code "229") (name "unconnected-(CN1-~{X1M}-Pad75)") (class "Default")
      (node (ref "CN1") (pin "75") (pinfunction "~{X1M}_75") (pintype "bidirectional"))
    )
    (net (code "230") (name "unconnected-(CN2-CE0-Pad36)") (class "Default")
      (node (ref "CN2") (pin "36") (pinfunction "CE0_36") (pintype "bidirectional"))
    )
    (net (code "231") (name "unconnected-(CN2-CE1-Pad26)") (class "Default")
      (node (ref "CN2") (pin "26") (pinfunction "CE1_26") (pintype "bidirectional"))
    )
    (net (code "232") (name "unconnected-(CN2-GPIO04-Pad7)") (class "Default")
      (node (ref "CN2") (pin "7") (pinfunction "GPIO04_7") (pintype "bidirectional"))
    )
    (net (code "233") (name "unconnected-(CN2-GPIO05-Pad29)") (class "Default")
      (node (ref "CN2") (pin "29") (pinfunction "GPIO05_29") (pintype "bidirectional"))
    )
    (net (code "234") (name "unconnected-(CN2-GPIO06-Pad31)") (class "Default")
      (node (ref "CN2") (pin "31") (pinfunction "GPIO06_31") (pintype "bidirectional"))
    )
    (net (code "235") (name "unconnected-(CN2-GPIO12-Pad32)") (class "Default")
      (node (ref "CN2") (pin "32") (pinfunction "GPIO12_32") (pintype "bidirectional"))
    )
    (net (code "236") (name "unconnected-(CN2-GPIO13-Pad33)") (class "Default")
      (node (ref "CN2") (pin "33") (pinfunction "GPIO13_33") (pintype "bidirectional"))
    )
    (net (code "237") (name "unconnected-(CN2-GPIO18-Pad12)") (class "Default")
      (node (ref "CN2") (pin "12") (pinfunction "GPIO18_12") (pintype "bidirectional"))
    )
    (net (code "238") (name "unconnected-(CN2-GPIO24-Pad18)") (class "Default")
      (node (ref "CN2") (pin "18") (pinfunction "GPIO24_18") (pintype "bidirectional"))
    )
    (net (code "239") (name "unconnected-(CN2-GPIO26-Pad37)") (class "Default")
      (node (ref "CN2") (pin "37") (pinfunction "GPIO26_37") (pintype "bidirectional"))
    )
    (net (code "240") (name "unconnected-(CN2-MISO-Pad35)") (class "Default")
      (node (ref "CN2") (pin "35") (pinfunction "MISO_35") (pintype "bidirectional"))
    )
    (net (code "241") (name "unconnected-(CN2-MOSI-Pad38)") (class "Default")
      (node (ref "CN2") (pin "38") (pinfunction "MOSI_38") (pintype "bidirectional"))
    )
    (net (code "242") (name "unconnected-(CN2-RXD-Pad10)") (class "Default")
      (node (ref "CN2") (pin "10") (pinfunction "RXD_10") (pintype "bidirectional"))
    )
    (net (code "243") (name "unconnected-(CN2-SCLK-Pad40)") (class "Default")
      (node (ref "CN2") (pin "40") (pinfunction "SCLK_40") (pintype "bidirectional"))
    )
    (net (code "244") (name "unconnected-(CN2-TXD-Pad8)") (class "Default")
      (node (ref "CN2") (pin "8") (pinfunction "TXD_8") (pintype "bidirectional"))
    )
    (net (code "245") (name "unconnected-(IC1A-A2-Pad46)") (class "Default")
      (node (ref "IC1") (pin "46") (pinfunction "A2_46") (pintype "bidirectional"))
    )
    (net (code "246") (name "unconnected-(IC1A-A3-Pad44)") (class "Default")
      (node (ref "IC1") (pin "44") (pinfunction "A3_44") (pintype "bidirectional"))
    )
    (net (code "247") (name "unconnected-(IC5C-GPIO26{slash}CLK0N-Pad26)") (class "Default")
      (node (ref "IC5") (pin "26") (pinfunction "GPIO26/CLK0N_26") (pintype "bidirectional"))
    )
    (net (code "248") (name "unconnected-(IC5C-GPIO28{slash}CLK1N-Pad28)") (class "Default")
      (node (ref "IC5") (pin "28") (pinfunction "GPIO28/CLK1N_28") (pintype "bidirectional"))
    )
    (net (code "249") (name "unconnected-(IC6-32KHZ-Pad1)") (class "Default")
      (node (ref "IC6") (pin "1") (pinfunction "32KHZ_1") (pintype "output"))
    )
    (net (code "250") (name "unconnected-(IC6-~{INT}{slash}SQW-Pad3)") (class "Default")
      (node (ref "IC6") (pin "3") (pinfunction "~{INT}/SQW_3") (pintype "output"))
    )
    (net (code "251") (name "unconnected-(IC6-~{RST}-Pad4)") (class "Default")
      (node (ref "IC6") (pin "4") (pinfunction "~{RST}_4") (pintype "input"))
    )
    (net (code "252") (name "unconnected-(IC8-CLKREF-Pad4)") (class "Default")
      (node (ref "IC8") (pin "4") (pinfunction "CLKREF_4") (pintype "output"))
    )
    (net (code "253") (name "unconnected-(IC8-X2-Pad8)") (class "Default")
      (node (ref "IC8") (pin "8") (pinfunction "X2_8") (pintype "input"))
    )
    (net (code "254") (name "unconnected-(IC9-NC{slash}FB-Pad4)") (class "Default")
      (node (ref "IC9") (pin "4") (pinfunction "NC/FB_4") (pintype "passive"))
    )
  )
)
